# RF08nv.net
KiCad netlist of a schematic drawn in EAGLE
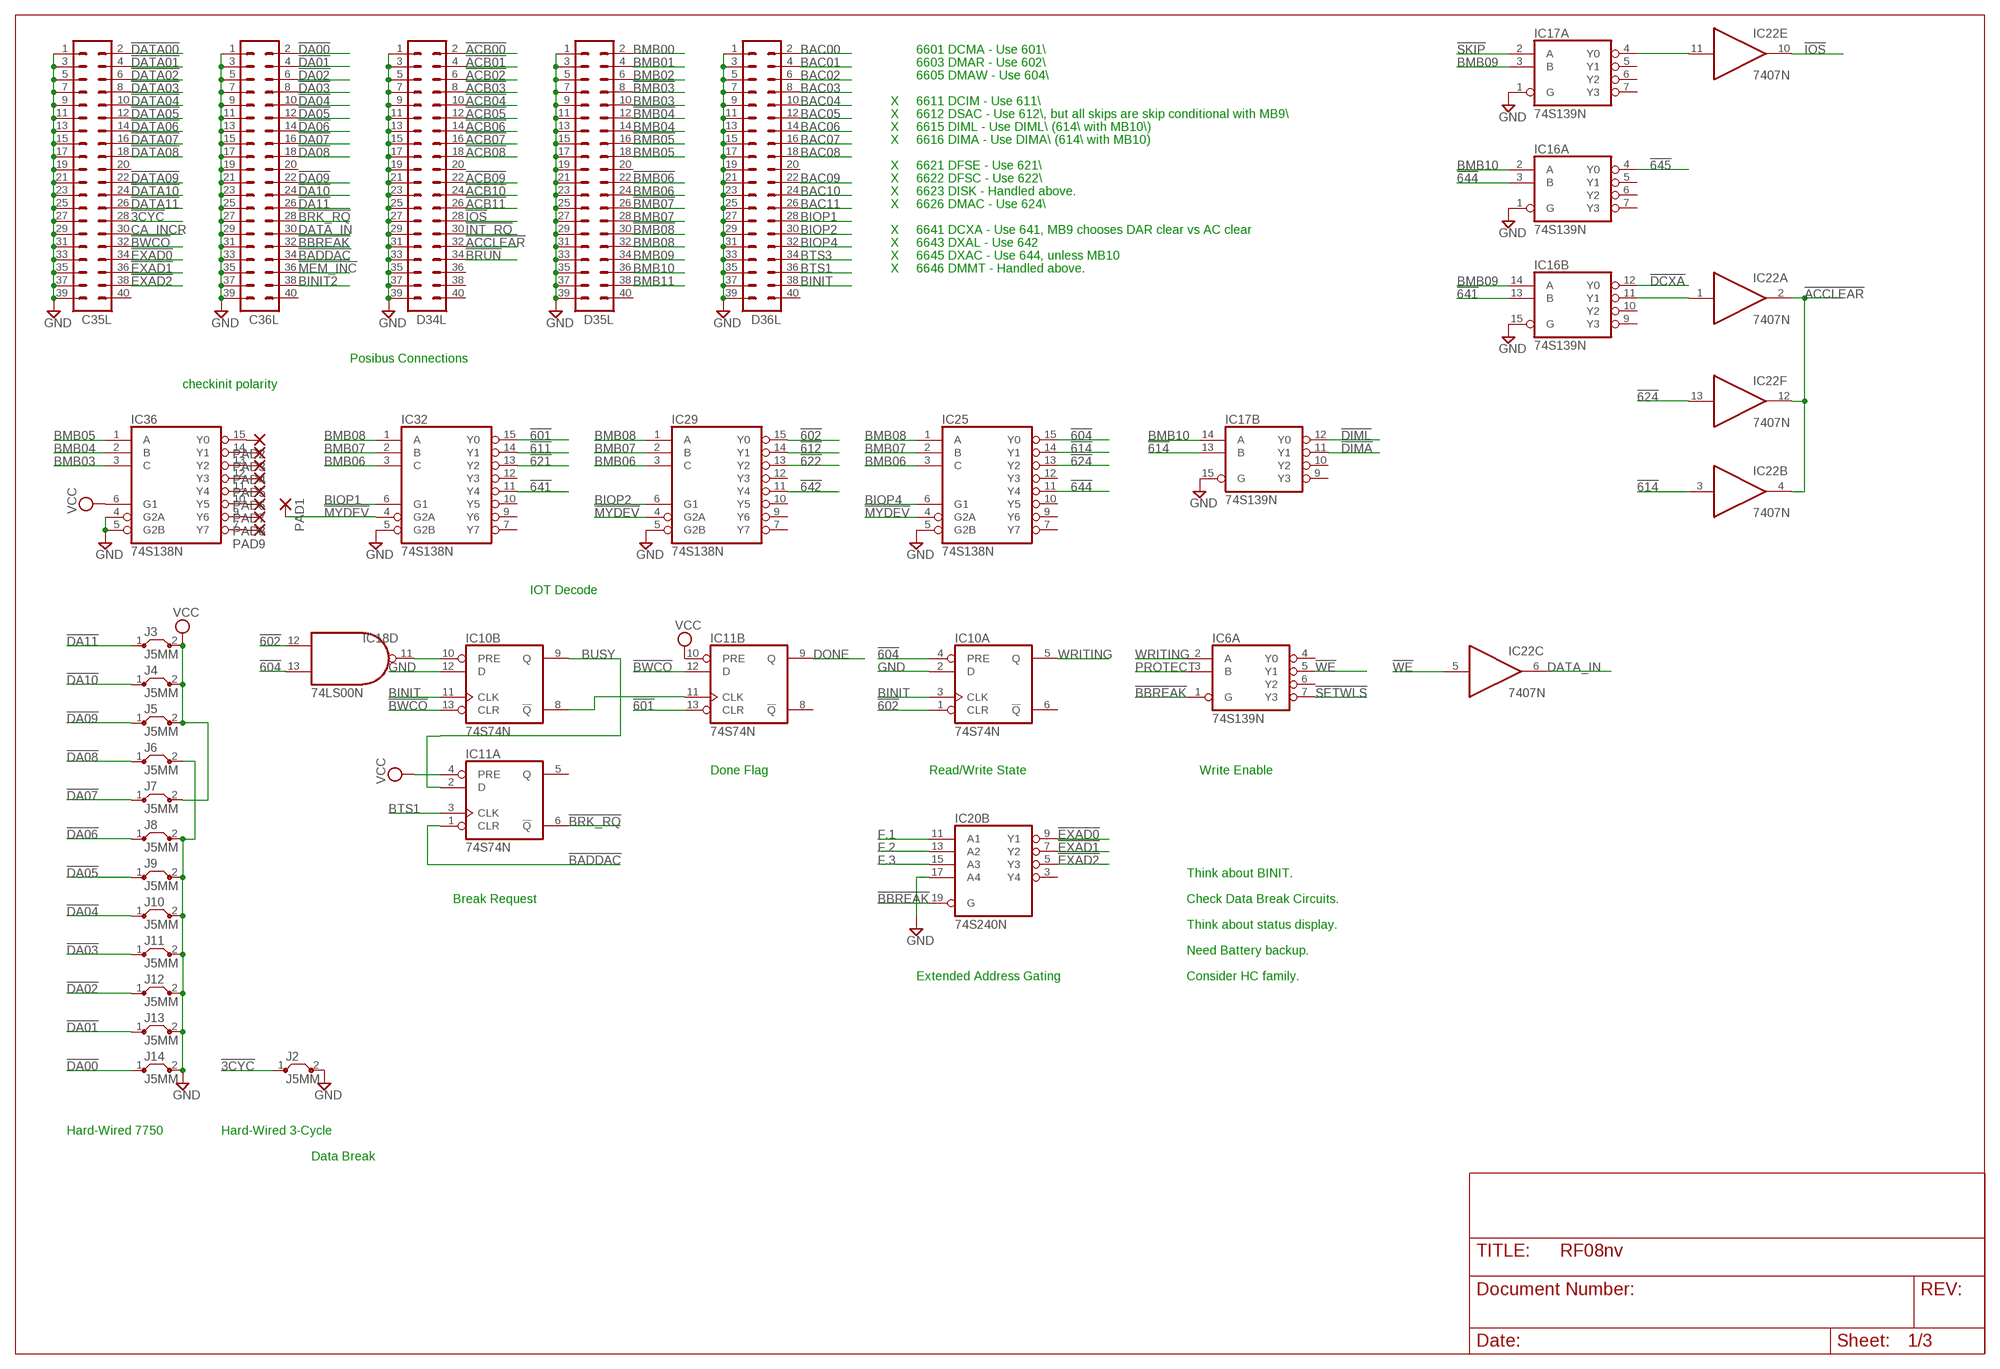
[diagram p0: schematic, sheet 1]
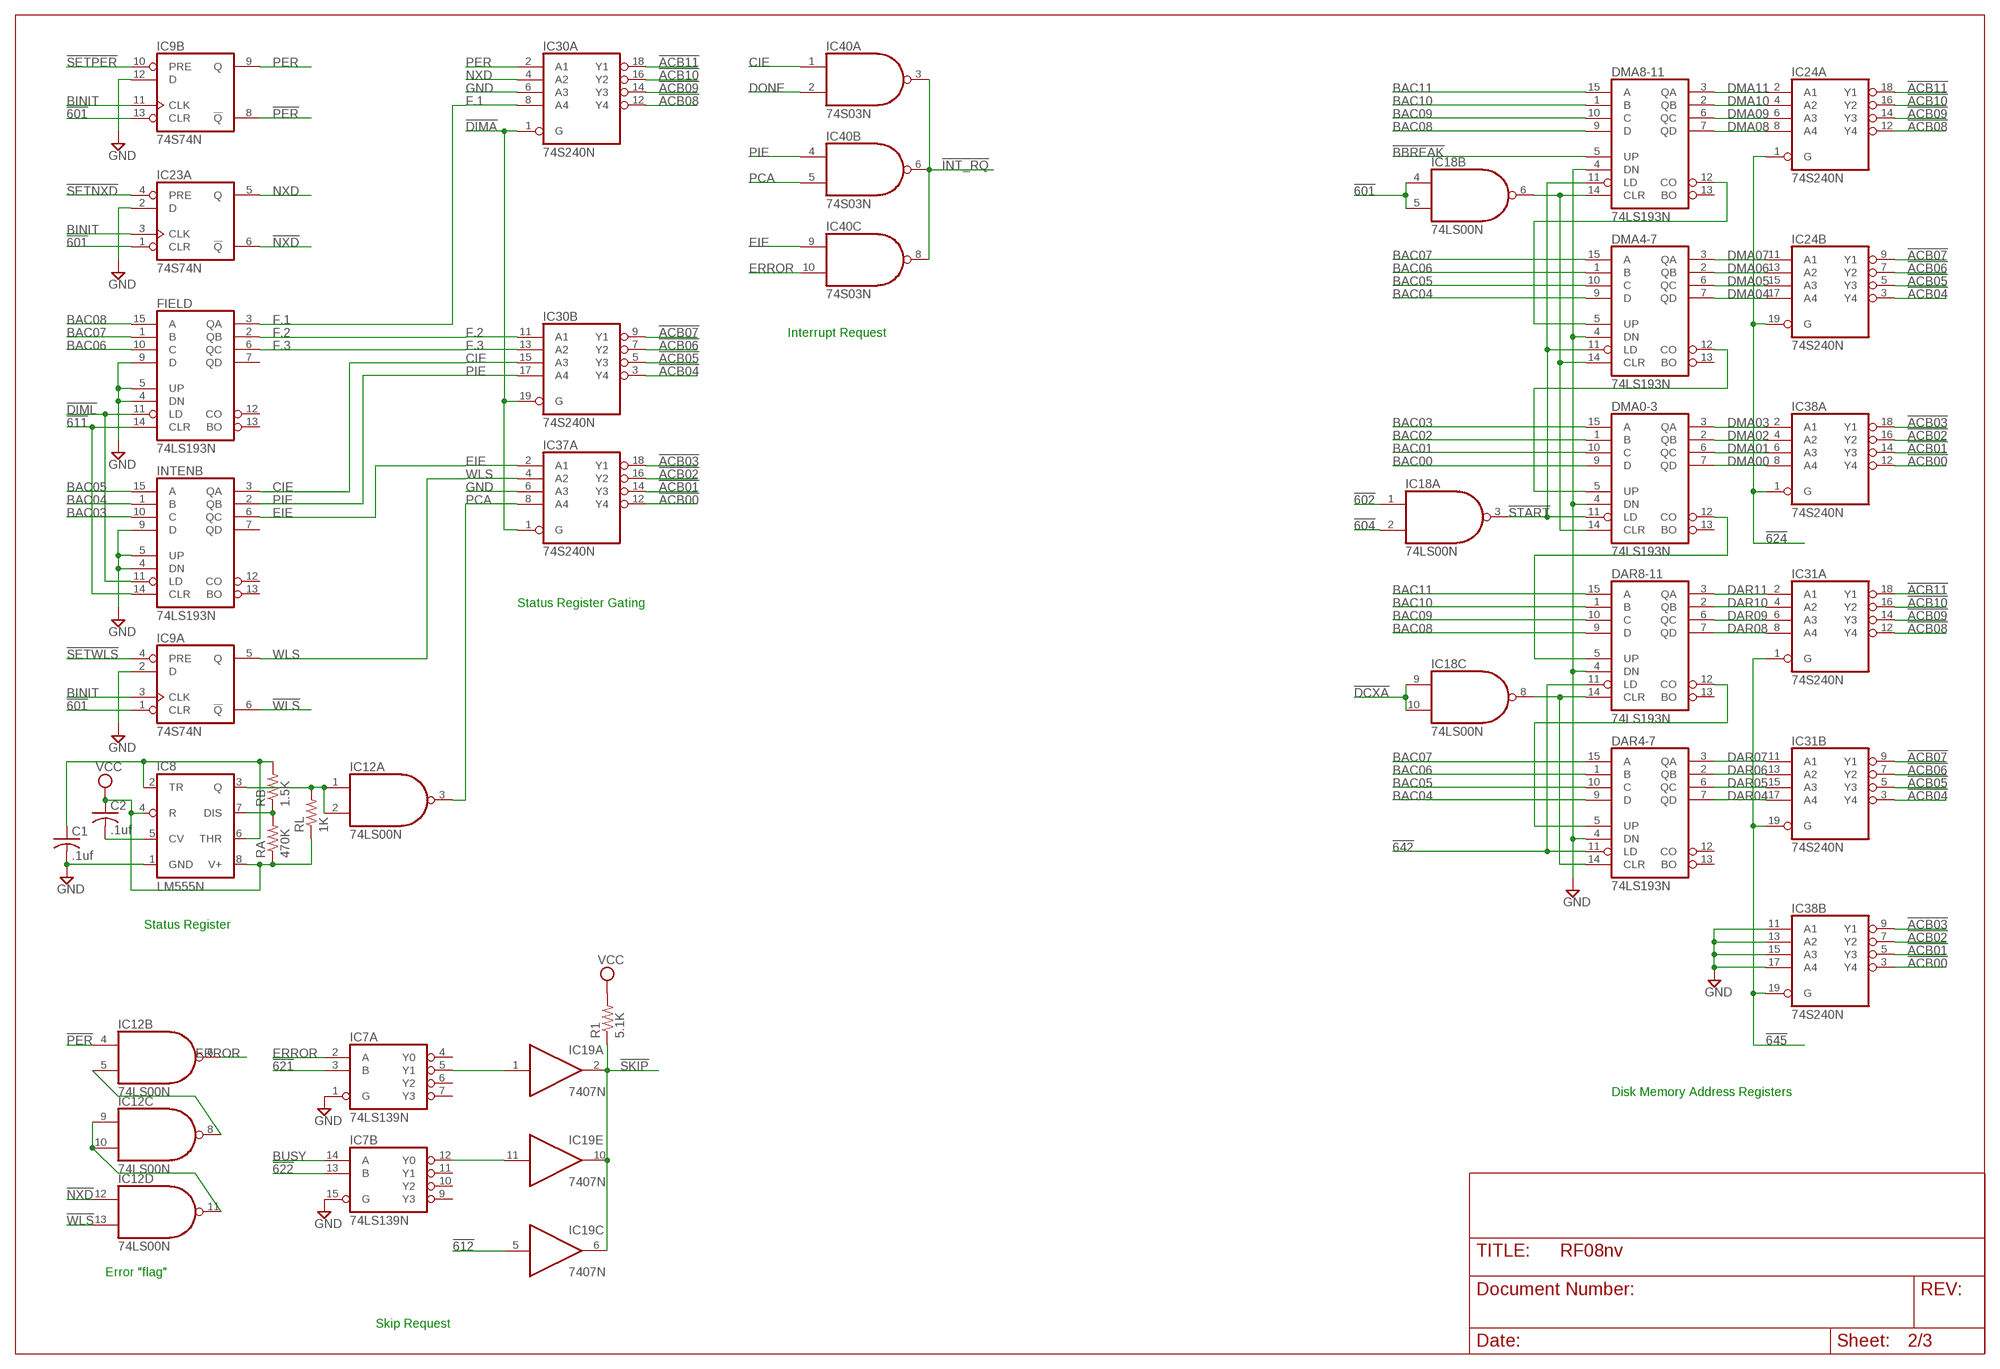
[diagram p1: schematic, sheet 2]
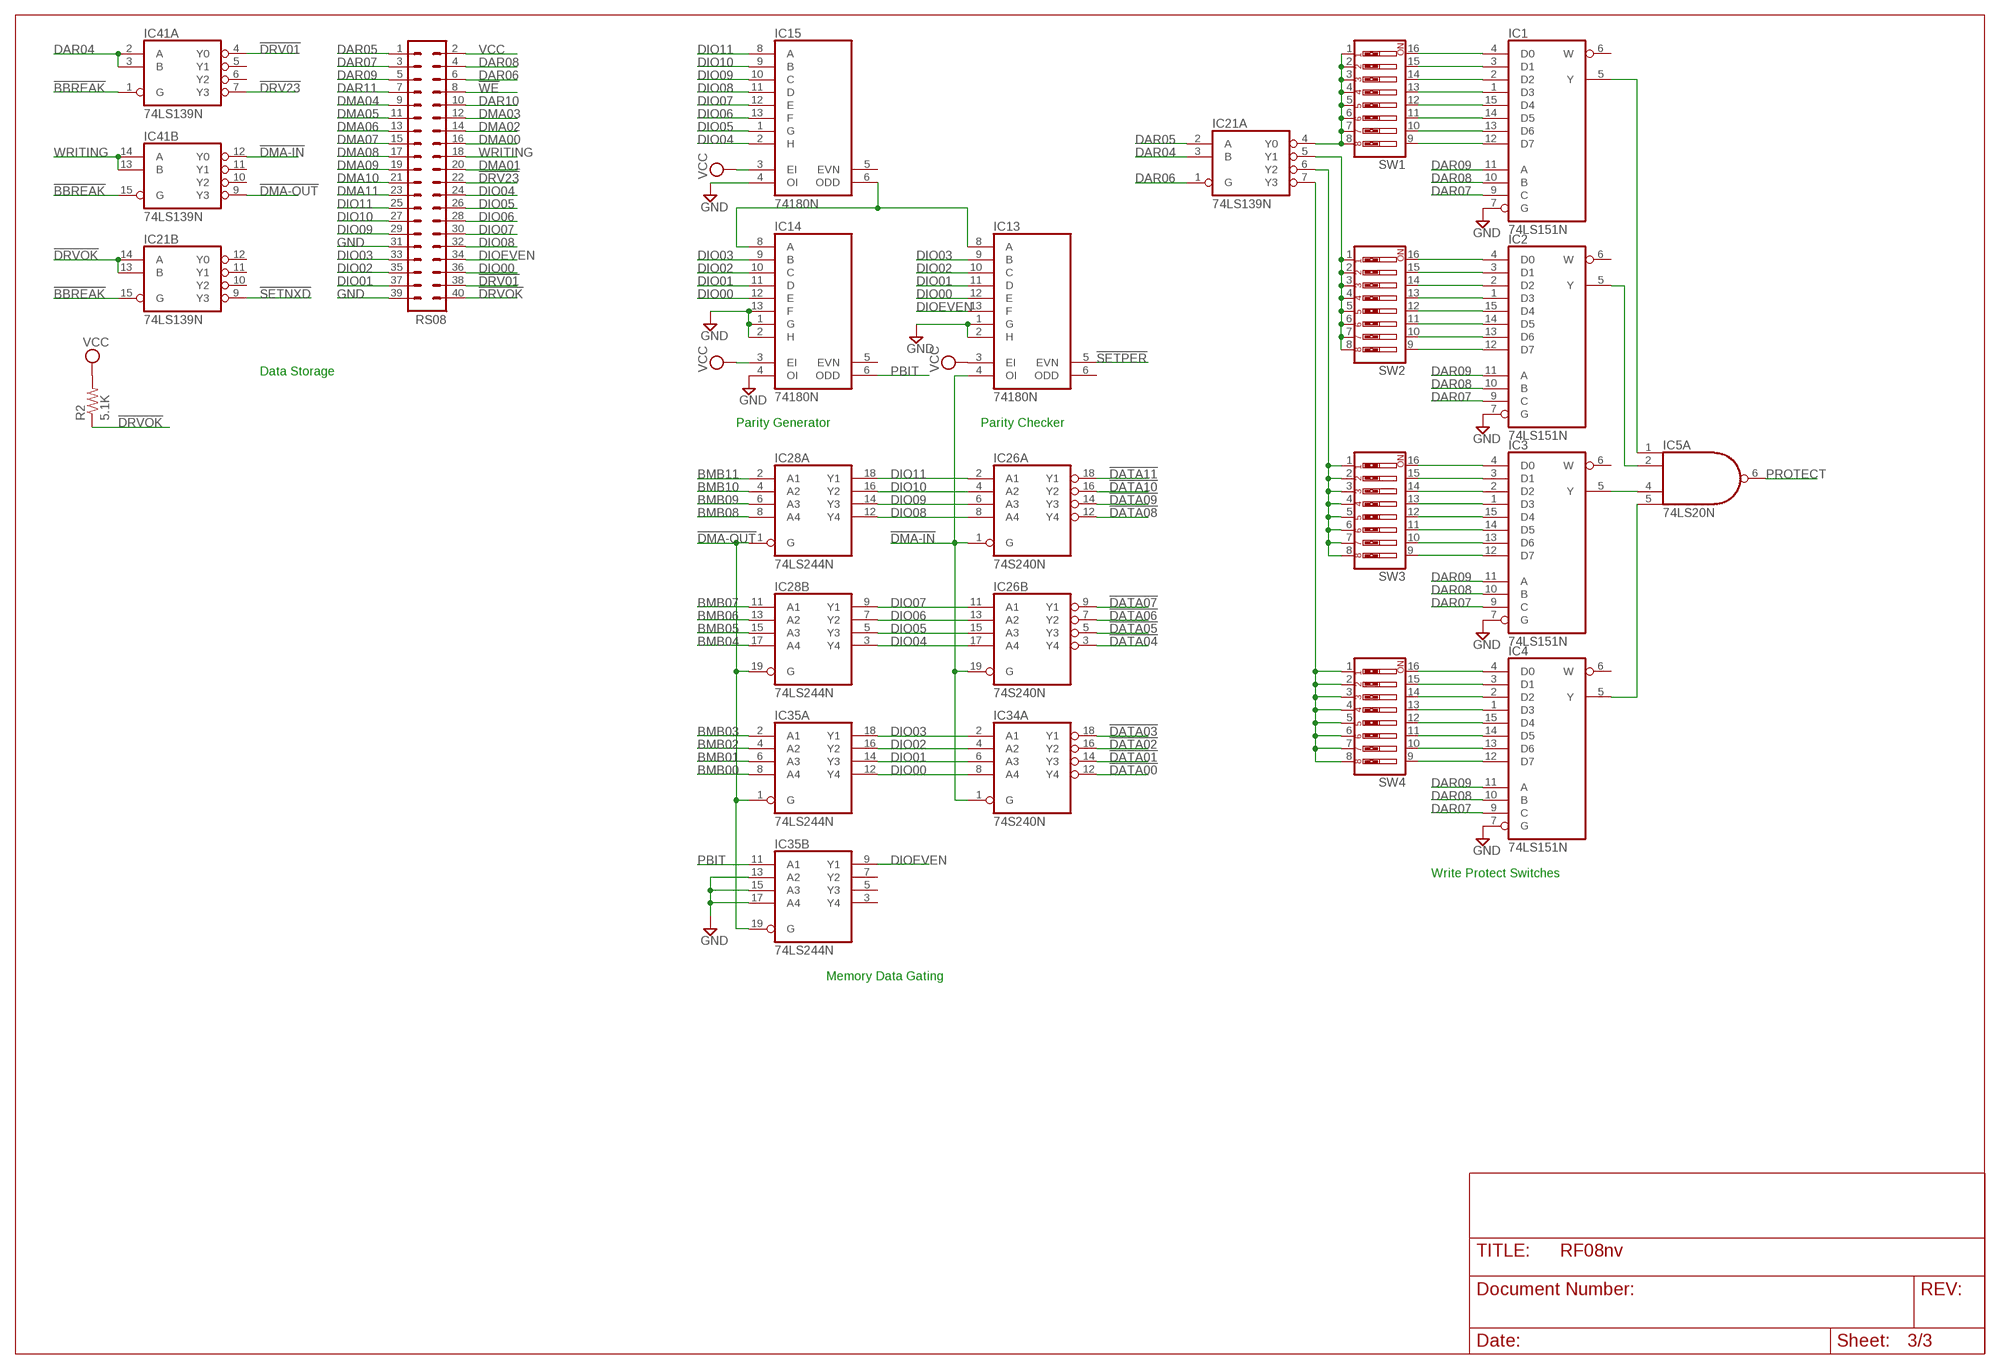
[diagram p2: schematic, sheet 3]

(export (version "E")
  (design (tool "Eeschema 10.0.6"))
  (components
    (comp (ref "IC1")
      (value "74LS151N")
      (footprint "eagle-import:DIL16")
      (libsource (lib "eagle-import") (part "74151NLS"))
    )
    (comp (ref "IC2")
      (value "74LS151N")
      (footprint "eagle-import:DIL16")
      (libsource (lib "eagle-import") (part "74151NLS"))
    )
    (comp (ref "IC3")
      (value "74LS151N")
      (footprint "eagle-import:DIL16")
      (libsource (lib "eagle-import") (part "74151NLS"))
    )
    (comp (ref "IC4")
      (value "74LS151N")
      (footprint "eagle-import:DIL16")
      (libsource (lib "eagle-import") (part "74151NLS"))
    )
    (comp (ref "IC5")
      (value "74LS20N")
      (footprint "eagle-import:DIL14")
      (libsource (lib "eagle-import") (part "7420NLS"))
    )
    (comp (ref "IC13")
      (value "74180N")
      (footprint "eagle-import:DIL14")
      (libsource (lib "eagle-import") (part "74180N"))
    )
    (comp (ref "IC14")
      (value "74180N")
      (footprint "eagle-import:DIL14")
      (libsource (lib "eagle-import") (part "74180N"))
    )
    (comp (ref "IC15")
      (value "74180N")
      (footprint "eagle-import:DIL14")
      (libsource (lib "eagle-import") (part "74180N"))
    )
    (comp (ref "IC21")
      (value "74LS139N")
      (footprint "eagle-import:DIL16")
      (libsource (lib "eagle-import") (part "74139NLS"))
    )
    (comp (ref "IC26")
      (value "74S240N")
      (footprint "eagle-import:DIL20")
      (libsource (lib "eagle-import") (part "74240NS"))
    )
    (comp (ref "IC28")
      (value "74LS244N")
      (footprint "eagle-import:DIL20")
      (libsource (lib "eagle-import") (part "74244NLS"))
    )
    (comp (ref "IC34")
      (value "74S240N")
      (footprint "eagle-import:DIL20")
      (libsource (lib "eagle-import") (part "74240NS"))
    )
    (comp (ref "IC35")
      (value "74LS244N")
      (footprint "eagle-import:DIL20")
      (libsource (lib "eagle-import") (part "74244NLS"))
    )
    (comp (ref "IC41")
      (value "74LS139N")
      (footprint "eagle-import:DIL16")
      (libsource (lib "eagle-import") (part "74139NLS"))
    )
    (comp (ref "R2")
      (value "5.1K")
      (footprint "eagle-import:0207_10")
      (libsource (lib "eagle-import") (part "R-US_0207/10"))
    )
    (comp (ref "RS08")
      (value "MA20-2")
      (footprint "eagle-import:MA20-2")
      (libsource (lib "eagle-import") (part "MA20-2"))
    )
    (comp (ref "SW1")
      (value "SW_DIP-8")
      (footprint "eagle-import:EDG-08")
      (libsource (lib "eagle-import") (part "SW_DIP-8"))
    )
    (comp (ref "SW2")
      (value "SW_DIP-8")
      (footprint "eagle-import:EDG-08")
      (libsource (lib "eagle-import") (part "SW_DIP-8"))
    )
    (comp (ref "SW3")
      (value "SW_DIP-8")
      (footprint "eagle-import:EDG-08")
      (libsource (lib "eagle-import") (part "SW_DIP-8"))
    )
    (comp (ref "SW4")
      (value "SW_DIP-8")
      (footprint "eagle-import:EDG-08")
      (libsource (lib "eagle-import") (part "SW_DIP-8"))
    )
    (comp (ref "C1")
      (value ".1uf")
      (footprint "eagle-import:C050-025X075")
      (libsource (lib "eagle-import") (part "C-US050-025X075"))
    )
    (comp (ref "C2")
      (value ".1uf")
      (footprint "eagle-import:C050-025X075")
      (libsource (lib "eagle-import") (part "C-US050-025X075"))
    )
    (comp (ref "DAR4-7")
      (value "74LS193N")
      (footprint "eagle-import:DIL16")
      (libsource (lib "eagle-import") (part "74192NLS"))
    )
    (comp (ref "DAR8-11")
      (value "74LS193N")
      (footprint "eagle-import:DIL16")
      (libsource (lib "eagle-import") (part "74192NLS"))
    )
    (comp (ref "DMA0-3")
      (value "74LS193N")
      (footprint "eagle-import:DIL16")
      (libsource (lib "eagle-import") (part "74192NLS"))
    )
    (comp (ref "DMA4-7")
      (value "74LS193N")
      (footprint "eagle-import:DIL16")
      (libsource (lib "eagle-import") (part "74192NLS"))
    )
    (comp (ref "DMA8-11")
      (value "74LS193N")
      (footprint "eagle-import:DIL16")
      (libsource (lib "eagle-import") (part "74192NLS"))
    )
    (comp (ref "FIELD")
      (value "74LS193N")
      (footprint "eagle-import:DIL16")
      (libsource (lib "eagle-import") (part "74192NLS"))
    )
    (comp (ref "IC7")
      (value "74LS139N")
      (footprint "eagle-import:DIL16")
      (libsource (lib "eagle-import") (part "74139NLS"))
    )
    (comp (ref "IC8")
      (value "LM555N")
      (footprint "eagle-import:DIL08")
      (libsource (lib "eagle-import") (part "555NLM"))
    )
    (comp (ref "IC9")
      (value "74S74N")
      (footprint "eagle-import:DIL14")
      (libsource (lib "eagle-import") (part "7474NS"))
    )
    (comp (ref "IC12")
      (value "74LS00N")
      (footprint "eagle-import:DIL14")
      (libsource (lib "eagle-import") (part "7400NLS"))
    )
    (comp (ref "IC18")
      (value "74LS00N")
      (footprint "eagle-import:DIL14")
      (libsource (lib "eagle-import") (part "7400NLS"))
    )
    (comp (ref "IC19")
      (value "7407N")
      (footprint "eagle-import:DIL14")
      (libsource (lib "eagle-import") (part "7407N"))
    )
    (comp (ref "IC23")
      (value "74S74N")
      (footprint "eagle-import:DIL14")
      (libsource (lib "eagle-import") (part "7474NS"))
    )
    (comp (ref "IC24")
      (value "74S240N")
      (footprint "eagle-import:DIL20")
      (libsource (lib "eagle-import") (part "74240NS"))
    )
    (comp (ref "IC30")
      (value "74S240N")
      (footprint "eagle-import:DIL20")
      (libsource (lib "eagle-import") (part "74240NS"))
    )
    (comp (ref "IC31")
      (value "74S240N")
      (footprint "eagle-import:DIL20")
      (libsource (lib "eagle-import") (part "74240NS"))
    )
    (comp (ref "IC37")
      (value "74S240N")
      (footprint "eagle-import:DIL20")
      (libsource (lib "eagle-import") (part "74240NS"))
    )
    (comp (ref "IC38")
      (value "74S240N")
      (footprint "eagle-import:DIL20")
      (libsource (lib "eagle-import") (part "74240NS"))
    )
    (comp (ref "IC40")
      (value "74S03N")
      (footprint "eagle-import:DIL14")
      (libsource (lib "eagle-import") (part "7403NS"))
    )
    (comp (ref "INTENB")
      (value "74LS193N")
      (footprint "eagle-import:DIL16")
      (libsource (lib "eagle-import") (part "74192NLS"))
    )
    (comp (ref "R1")
      (value "5.1K")
      (footprint "eagle-import:0207_10")
      (libsource (lib "eagle-import") (part "R-US_0207/10"))
    )
    (comp (ref "RA")
      (value "470K")
      (footprint "eagle-import:0207_10")
      (libsource (lib "eagle-import") (part "R-US_0207/10"))
    )
    (comp (ref "RB")
      (value "1.5K")
      (footprint "eagle-import:0207_10")
      (libsource (lib "eagle-import") (part "R-US_0207/10"))
    )
    (comp (ref "RL")
      (value "1K")
      (footprint "eagle-import:0207_10")
      (libsource (lib "eagle-import") (part "R-US_0207/10"))
    )
    (comp (ref "C35L")
      (value "MA20-2")
      (footprint "eagle-import:MA20-2")
      (libsource (lib "eagle-import") (part "MA20-2"))
    )
    (comp (ref "C36L")
      (value "MA20-2")
      (footprint "eagle-import:MA20-2")
      (libsource (lib "eagle-import") (part "MA20-2"))
    )
    (comp (ref "D34L")
      (value "MA20-2")
      (footprint "eagle-import:MA20-2")
      (libsource (lib "eagle-import") (part "MA20-2"))
    )
    (comp (ref "D35L")
      (value "MA20-2")
      (footprint "eagle-import:MA20-2")
      (libsource (lib "eagle-import") (part "MA20-2"))
    )
    (comp (ref "D36L")
      (value "MA20-2")
      (footprint "eagle-import:MA20-2")
      (libsource (lib "eagle-import") (part "MA20-2"))
    )
    (comp (ref "IC6")
      (value "74S139N")
      (footprint "eagle-import:DIL16")
      (libsource (lib "eagle-import") (part "74139NS"))
    )
    (comp (ref "IC10")
      (value "74S74N")
      (footprint "eagle-import:DIL14")
      (libsource (lib "eagle-import") (part "7474NS"))
    )
    (comp (ref "IC11")
      (value "74S74N")
      (footprint "eagle-import:DIL14")
      (libsource (lib "eagle-import") (part "7474NS"))
    )
    (comp (ref "IC16")
      (value "74S139N")
      (footprint "eagle-import:DIL16")
      (libsource (lib "eagle-import") (part "74139NS"))
    )
    (comp (ref "IC17")
      (value "74S139N")
      (footprint "eagle-import:DIL16")
      (libsource (lib "eagle-import") (part "74139NS"))
    )
    (comp (ref "IC20")
      (value "74S240N")
      (footprint "eagle-import:DIL20")
      (libsource (lib "eagle-import") (part "74240NS"))
    )
    (comp (ref "IC22")
      (value "7407N")
      (footprint "eagle-import:DIL14")
      (libsource (lib "eagle-import") (part "7407N"))
    )
    (comp (ref "IC25")
      (value "74S138N")
      (footprint "eagle-import:DIL16")
      (libsource (lib "eagle-import") (part "74138NS"))
    )
    (comp (ref "IC29")
      (value "74S138N")
      (footprint "eagle-import:DIL16")
      (libsource (lib "eagle-import") (part "74138NS"))
    )
    (comp (ref "IC32")
      (value "74S138N")
      (footprint "eagle-import:DIL16")
      (libsource (lib "eagle-import") (part "74138NS"))
    )
    (comp (ref "IC36")
      (value "74S138N")
      (footprint "eagle-import:DIL16")
      (libsource (lib "eagle-import") (part "74138NS"))
    )
    (comp (ref "J2")
      (value "J5MM")
      (footprint "eagle-import:05")
      (libsource (lib "eagle-import") (part "J5MM"))
    )
    (comp (ref "J3")
      (value "J5MM")
      (footprint "eagle-import:05")
      (libsource (lib "eagle-import") (part "J5MM"))
    )
    (comp (ref "J4")
      (value "J5MM")
      (footprint "eagle-import:05")
      (libsource (lib "eagle-import") (part "J5MM"))
    )
    (comp (ref "J5")
      (value "J5MM")
      (footprint "eagle-import:05")
      (libsource (lib "eagle-import") (part "J5MM"))
    )
    (comp (ref "J6")
      (value "J5MM")
      (footprint "eagle-import:05")
      (libsource (lib "eagle-import") (part "J5MM"))
    )
    (comp (ref "J7")
      (value "J5MM")
      (footprint "eagle-import:05")
      (libsource (lib "eagle-import") (part "J5MM"))
    )
    (comp (ref "J8")
      (value "J5MM")
      (footprint "eagle-import:05")
      (libsource (lib "eagle-import") (part "J5MM"))
    )
    (comp (ref "J9")
      (value "J5MM")
      (footprint "eagle-import:05")
      (libsource (lib "eagle-import") (part "J5MM"))
    )
    (comp (ref "J10")
      (value "J5MM")
      (footprint "eagle-import:05")
      (libsource (lib "eagle-import") (part "J5MM"))
    )
    (comp (ref "J11")
      (value "J5MM")
      (footprint "eagle-import:05")
      (libsource (lib "eagle-import") (part "J5MM"))
    )
    (comp (ref "J12")
      (value "J5MM")
      (footprint "eagle-import:05")
      (libsource (lib "eagle-import") (part "J5MM"))
    )
    (comp (ref "J13")
      (value "J5MM")
      (footprint "eagle-import:05")
      (libsource (lib "eagle-import") (part "J5MM"))
    )
    (comp (ref "J14")
      (value "J5MM")
      (footprint "eagle-import:05")
      (libsource (lib "eagle-import") (part "J5MM"))
    )
    (comp (ref "PAD1")
      (value "1,6/0,8")
      (footprint "eagle-import:1,6_0,8")
      (libsource (lib "eagle-import") (part "1,6/0,8"))
    )
    (comp (ref "PAD2")
      (value "1,6/0,8")
      (footprint "eagle-import:1,6_0,8")
      (libsource (lib "eagle-import") (part "1,6/0,8"))
    )
    (comp (ref "PAD3")
      (value "1,6/0,8")
      (footprint "eagle-import:1,6_0,8")
      (libsource (lib "eagle-import") (part "1,6/0,8"))
    )
    (comp (ref "PAD4")
      (value "1,6/0,8")
      (footprint "eagle-import:1,6_0,8")
      (libsource (lib "eagle-import") (part "1,6/0,8"))
    )
    (comp (ref "PAD5")
      (value "1,6/0,8")
      (footprint "eagle-import:1,6_0,8")
      (libsource (lib "eagle-import") (part "1,6/0,8"))
    )
    (comp (ref "PAD6")
      (value "1,6/0,8")
      (footprint "eagle-import:1,6_0,8")
      (libsource (lib "eagle-import") (part "1,6/0,8"))
    )
    (comp (ref "PAD7")
      (value "1,6/0,8")
      (footprint "eagle-import:1,6_0,8")
      (libsource (lib "eagle-import") (part "1,6/0,8"))
    )
    (comp (ref "PAD8")
      (value "1,6/0,8")
      (footprint "eagle-import:1,6_0,8")
      (libsource (lib "eagle-import") (part "1,6/0,8"))
    )
    (comp (ref "PAD9")
      (value "1,6/0,8")
      (footprint "eagle-import:1,6_0,8")
      (libsource (lib "eagle-import") (part "1,6/0,8"))
    )
  )
  (nets
    (net (code "1") (name "BAC00") (class "Default")
      (node (ref "D36L") (pin "2") (pinfunction "2_2") (pintype "passive"))
      (node (ref "DMA0-3") (pin "9") (pinfunction "D_9") (pintype "input"))
    )
    (net (code "2") (name "BAC01") (class "Default")
      (node (ref "D36L") (pin "4") (pinfunction "4_4") (pintype "passive"))
      (node (ref "DMA0-3") (pin "10") (pinfunction "C_10") (pintype "input"))
    )
    (net (code "3") (name "BAC02") (class "Default")
      (node (ref "D36L") (pin "6") (pinfunction "6_6") (pintype "passive"))
      (node (ref "DMA0-3") (pin "1") (pinfunction "B_1") (pintype "input"))
    )
    (net (code "4") (name "BAC03") (class "Default")
      (node (ref "D36L") (pin "8") (pinfunction "8_8") (pintype "passive"))
      (node (ref "DMA0-3") (pin "15") (pinfunction "A_15") (pintype "input"))
      (node (ref "INTENB") (pin "10") (pinfunction "C_10") (pintype "input"))
    )
    (net (code "5") (name "BAC04") (class "Default")
      (node (ref "D36L") (pin "10") (pinfunction "10_10") (pintype "passive"))
      (node (ref "DAR4-7") (pin "9") (pinfunction "D_9") (pintype "input"))
      (node (ref "DMA4-7") (pin "9") (pinfunction "D_9") (pintype "input"))
      (node (ref "INTENB") (pin "1") (pinfunction "B_1") (pintype "input"))
    )
    (net (code "6") (name "BAC05") (class "Default")
      (node (ref "D36L") (pin "12") (pinfunction "12_12") (pintype "passive"))
      (node (ref "DAR4-7") (pin "10") (pinfunction "C_10") (pintype "input"))
      (node (ref "DMA4-7") (pin "10") (pinfunction "C_10") (pintype "input"))
      (node (ref "INTENB") (pin "15") (pinfunction "A_15") (pintype "input"))
    )
    (net (code "7") (name "BAC06") (class "Default")
      (node (ref "D36L") (pin "14") (pinfunction "14_14") (pintype "passive"))
      (node (ref "DAR4-7") (pin "1") (pinfunction "B_1") (pintype "input"))
      (node (ref "DMA4-7") (pin "1") (pinfunction "B_1") (pintype "input"))
      (node (ref "FIELD") (pin "10") (pinfunction "C_10") (pintype "input"))
    )
    (net (code "8") (name "BAC07") (class "Default")
      (node (ref "D36L") (pin "16") (pinfunction "16_16") (pintype "passive"))
      (node (ref "DAR4-7") (pin "15") (pinfunction "A_15") (pintype "input"))
      (node (ref "DMA4-7") (pin "15") (pinfunction "A_15") (pintype "input"))
      (node (ref "FIELD") (pin "1") (pinfunction "B_1") (pintype "input"))
    )
    (net (code "9") (name "BAC08") (class "Default")
      (node (ref "D36L") (pin "18") (pinfunction "18_18") (pintype "passive"))
      (node (ref "DAR8-11") (pin "9") (pinfunction "D_9") (pintype "input"))
      (node (ref "DMA8-11") (pin "9") (pinfunction "D_9") (pintype "input"))
      (node (ref "FIELD") (pin "15") (pinfunction "A_15") (pintype "input"))
    )
    (net (code "10") (name "BAC09") (class "Default")
      (node (ref "D36L") (pin "22") (pinfunction "22_22") (pintype "passive"))
      (node (ref "DAR8-11") (pin "10") (pinfunction "C_10") (pintype "input"))
      (node (ref "DMA8-11") (pin "10") (pinfunction "C_10") (pintype "input"))
    )
    (net (code "11") (name "BAC10") (class "Default")
      (node (ref "D36L") (pin "24") (pinfunction "24_24") (pintype "passive"))
      (node (ref "DAR8-11") (pin "1") (pinfunction "B_1") (pintype "input"))
      (node (ref "DMA8-11") (pin "1") (pinfunction "B_1") (pintype "input"))
    )
    (net (code "12") (name "BAC11") (class "Default")
      (node (ref "D36L") (pin "26") (pinfunction "26_26") (pintype "passive"))
      (node (ref "DAR8-11") (pin "15") (pinfunction "A_15") (pintype "input"))
      (node (ref "DMA8-11") (pin "15") (pinfunction "A_15") (pintype "input"))
    )
    (net (code "13") (name "BINIT") (class "Default")
      (node (ref "D36L") (pin "38") (pinfunction "38_38") (pintype "passive"))
      (node (ref "IC10") (pin "11") (pinfunction "CLK_11") (pintype "input"))
      (node (ref "IC10") (pin "3") (pinfunction "CLK_3") (pintype "input"))
      (node (ref "IC23") (pin "3") (pinfunction "CLK_3") (pintype "input"))
      (node (ref "IC9") (pin "11") (pinfunction "CLK_11") (pintype "input"))
      (node (ref "IC9") (pin "3") (pinfunction "CLK_3") (pintype "input"))
    )
    (net (code "14") (name "BINIT2") (class "Default")
      (node (ref "C36L") (pin "38") (pinfunction "38_38") (pintype "passive"))
    )
    (net (code "15") (name "BIOP1") (class "Default")
      (node (ref "D36L") (pin "28") (pinfunction "28_28") (pintype "passive"))
      (node (ref "IC32") (pin "6") (pinfunction "G1_6") (pintype "input"))
    )
    (net (code "16") (name "BIOP2") (class "Default")
      (node (ref "D36L") (pin "30") (pinfunction "30_30") (pintype "passive"))
      (node (ref "IC29") (pin "6") (pinfunction "G1_6") (pintype "input"))
    )
    (net (code "17") (name "BIOP4") (class "Default")
      (node (ref "D36L") (pin "32") (pinfunction "32_32") (pintype "passive"))
      (node (ref "IC25") (pin "6") (pinfunction "G1_6") (pintype "input"))
    )
    (net (code "18") (name "BMB00") (class "Default")
      (node (ref "D35L") (pin "2") (pinfunction "2_2") (pintype "passive"))
      (node (ref "IC35") (pin "8") (pinfunction "A4_8") (pintype "input"))
    )
    (net (code "19") (name "BMB01") (class "Default")
      (node (ref "D35L") (pin "4") (pinfunction "4_4") (pintype "passive"))
      (node (ref "IC35") (pin "6") (pinfunction "A3_6") (pintype "input"))
    )
    (net (code "20") (name "BMB02") (class "Default")
      (node (ref "D35L") (pin "6") (pinfunction "6_6") (pintype "passive"))
      (node (ref "IC35") (pin "4") (pinfunction "A2_4") (pintype "input"))
    )
    (net (code "21") (name "BMB03") (class "Default")
      (node (ref "D35L") (pin "10") (pinfunction "10_10") (pintype "passive"))
      (node (ref "IC35") (pin "2") (pinfunction "A1_2") (pintype "input"))
      (node (ref "IC36") (pin "3") (pinfunction "C_3") (pintype "input"))
    )
    (net (code "22") (name "BMB04") (class "Default")
      (node (ref "D35L") (pin "14") (pinfunction "14_14") (pintype "passive"))
      (node (ref "IC28") (pin "17") (pinfunction "A4_17") (pintype "input"))
      (node (ref "IC36") (pin "2") (pinfunction "B_2") (pintype "input"))
    )
    (net (code "23") (name "BMB05") (class "Default")
      (node (ref "D35L") (pin "18") (pinfunction "18_18") (pintype "passive"))
      (node (ref "IC28") (pin "15") (pinfunction "A3_15") (pintype "input"))
      (node (ref "IC36") (pin "1") (pinfunction "A_1") (pintype "input"))
    )
    (net (code "24") (name "BMB06") (class "Default")
      (node (ref "D35L") (pin "24") (pinfunction "24_24") (pintype "passive"))
      (node (ref "IC25") (pin "3") (pinfunction "C_3") (pintype "input"))
      (node (ref "IC28") (pin "13") (pinfunction "A2_13") (pintype "input"))
      (node (ref "IC29") (pin "3") (pinfunction "C_3") (pintype "input"))
      (node (ref "IC32") (pin "3") (pinfunction "C_3") (pintype "input"))
    )
    (net (code "25") (name "BMB07") (class "Default")
      (node (ref "D35L") (pin "28") (pinfunction "28_28") (pintype "passive"))
      (node (ref "IC25") (pin "2") (pinfunction "B_2") (pintype "input"))
      (node (ref "IC28") (pin "11") (pinfunction "A1_11") (pintype "input"))
      (node (ref "IC29") (pin "2") (pinfunction "B_2") (pintype "input"))
      (node (ref "IC32") (pin "2") (pinfunction "B_2") (pintype "input"))
    )
    (net (code "26") (name "BMB08") (class "Default")
      (node (ref "D35L") (pin "32") (pinfunction "32_32") (pintype "passive"))
      (node (ref "IC25") (pin "1") (pinfunction "A_1") (pintype "input"))
      (node (ref "IC28") (pin "8") (pinfunction "A4_8") (pintype "input"))
      (node (ref "IC29") (pin "1") (pinfunction "A_1") (pintype "input"))
      (node (ref "IC32") (pin "1") (pinfunction "A_1") (pintype "input"))
    )
    (net (code "27") (name "BMB09") (class "Default")
      (node (ref "D35L") (pin "34") (pinfunction "34_34") (pintype "passive"))
      (node (ref "IC16") (pin "14") (pinfunction "A_14") (pintype "input"))
      (node (ref "IC17") (pin "3") (pinfunction "B_3") (pintype "input"))
      (node (ref "IC28") (pin "6") (pinfunction "A3_6") (pintype "input"))
    )
    (net (code "28") (name "BMB10") (class "Default")
      (node (ref "D35L") (pin "36") (pinfunction "36_36") (pintype "passive"))
      (node (ref "IC16") (pin "2") (pinfunction "A_2") (pintype "input"))
      (node (ref "IC17") (pin "14") (pinfunction "A_14") (pintype "input"))
      (node (ref "IC28") (pin "4") (pinfunction "A2_4") (pintype "input"))
    )
    (net (code "29") (name "BMB11") (class "Default")
      (node (ref "D35L") (pin "38") (pinfunction "38_38") (pintype "passive"))
      (node (ref "IC28") (pin "2") (pinfunction "A1_2") (pintype "input"))
    )
    (net (code "30") (name "BTS1") (class "Default")
      (node (ref "D36L") (pin "36") (pinfunction "36_36") (pintype "passive"))
      (node (ref "IC11") (pin "3") (pinfunction "CLK_3") (pintype "input"))
    )
    (net (code "31") (name "BTS3") (class "Default")
      (node (ref "D36L") (pin "34") (pinfunction "34_34") (pintype "passive"))
    )
    (net (code "32") (name "BUSY") (class "Default")
      (node (ref "IC10") (pin "9") (pinfunction "Q_9") (pintype "output"))
      (node (ref "IC11") (pin "2") (pinfunction "D_2") (pintype "input"))
      (node (ref "IC7") (pin "14") (pinfunction "A_14") (pintype "input"))
    )
    (net (code "33") (name "CA_INCR") (class "Default")
      (node (ref "C35L") (pin "30") (pinfunction "30_30") (pintype "passive"))
    )
    (net (code "34") (name "CIE") (class "Default")
      (node (ref "IC30") (pin "15") (pinfunction "A3_15") (pintype "input"))
      (node (ref "IC40") (pin "1") (pinfunction "I0_1") (pintype "input"))
      (node (ref "INTENB") (pin "3") (pinfunction "QA_3") (pintype "output"))
    )
    (net (code "35") (name "DAR04") (class "Default")
      (node (ref "DAR4-7") (pin "7") (pinfunction "QD_7") (pintype "output"))
      (node (ref "IC21") (pin "3") (pinfunction "B_3") (pintype "input"))
      (node (ref "IC31") (pin "17") (pinfunction "A4_17") (pintype "input"))
      (node (ref "IC41") (pin "2") (pinfunction "A_2") (pintype "input"))
      (node (ref "IC41") (pin "3") (pinfunction "B_3") (pintype "input"))
    )
    (net (code "36") (name "DAR05") (class "Default")
      (node (ref "DAR4-7") (pin "6") (pinfunction "QC_6") (pintype "output"))
      (node (ref "IC21") (pin "2") (pinfunction "A_2") (pintype "input"))
      (node (ref "IC31") (pin "15") (pinfunction "A3_15") (pintype "input"))
      (node (ref "RS08") (pin "1") (pinfunction "1_1") (pintype "passive"))
    )
    (net (code "37") (name "DAR06") (class "Default")
      (node (ref "DAR4-7") (pin "2") (pinfunction "QB_2") (pintype "output"))
      (node (ref "IC21") (pin "1") (pinfunction "G_1") (pintype "input"))
      (node (ref "IC31") (pin "13") (pinfunction "A2_13") (pintype "input"))
      (node (ref "RS08") (pin "6") (pinfunction "6_6") (pintype "passive"))
    )
    (net (code "38") (name "DAR07") (class "Default")
      (node (ref "DAR4-7") (pin "3") (pinfunction "QA_3") (pintype "output"))
      (node (ref "IC1") (pin "9") (pinfunction "C_9") (pintype "input"))
      (node (ref "IC2") (pin "9") (pinfunction "C_9") (pintype "input"))
      (node (ref "IC3") (pin "9") (pinfunction "C_9") (pintype "input"))
      (node (ref "IC31") (pin "11") (pinfunction "A1_11") (pintype "input"))
      (node (ref "IC4") (pin "9") (pinfunction "C_9") (pintype "input"))
      (node (ref "RS08") (pin "3") (pinfunction "3_3") (pintype "passive"))
    )
    (net (code "39") (name "DAR08") (class "Default")
      (node (ref "DAR8-11") (pin "7") (pinfunction "QD_7") (pintype "output"))
      (node (ref "IC1") (pin "10") (pinfunction "B_10") (pintype "input"))
      (node (ref "IC2") (pin "10") (pinfunction "B_10") (pintype "input"))
      (node (ref "IC3") (pin "10") (pinfunction "B_10") (pintype "input"))
      (node (ref "IC31") (pin "8") (pinfunction "A4_8") (pintype "input"))
      (node (ref "IC4") (pin "10") (pinfunction "B_10") (pintype "input"))
      (node (ref "RS08") (pin "4") (pinfunction "4_4") (pintype "passive"))
    )
    (net (code "40") (name "DAR09") (class "Default")
      (node (ref "DAR8-11") (pin "6") (pinfunction "QC_6") (pintype "output"))
      (node (ref "IC1") (pin "11") (pinfunction "A_11") (pintype "input"))
      (node (ref "IC2") (pin "11") (pinfunction "A_11") (pintype "input"))
      (node (ref "IC3") (pin "11") (pinfunction "A_11") (pintype "input"))
      (node (ref "IC31") (pin "6") (pinfunction "A3_6") (pintype "input"))
      (node (ref "IC4") (pin "11") (pinfunction "A_11") (pintype "input"))
      (node (ref "RS08") (pin "5") (pinfunction "5_5") (pintype "passive"))
    )
    (net (code "41") (name "DAR10") (class "Default")
      (node (ref "DAR8-11") (pin "2") (pinfunction "QB_2") (pintype "output"))
      (node (ref "IC31") (pin "4") (pinfunction "A2_4") (pintype "input"))
      (node (ref "RS08") (pin "10") (pinfunction "10_10") (pintype "passive"))
    )
    (net (code "42") (name "DAR11") (class "Default")
      (node (ref "DAR8-11") (pin "3") (pinfunction "QA_3") (pintype "output"))
      (node (ref "IC31") (pin "2") (pinfunction "A1_2") (pintype "input"))
      (node (ref "RS08") (pin "7") (pinfunction "7_7") (pintype "passive"))
    )
    (net (code "43") (name "DATA_IN") (class "Default")
      (node (ref "C36L") (pin "30") (pinfunction "30_30") (pintype "passive"))
      (node (ref "IC22") (pin "6") (pinfunction "O_6") (pintype "open_collector"))
    )
    (net (code "44") (name "DIO00") (class "Default")
      (node (ref "IC13") (pin "12") (pinfunction "E_12") (pintype "input"))
      (node (ref "IC14") (pin "12") (pinfunction "E_12") (pintype "input"))
      (node (ref "IC34") (pin "8") (pinfunction "A4_8") (pintype "input"))
      (node (ref "IC35") (pin "12") (pinfunction "Y4_12") (pintype "tri_state"))
      (node (ref "RS08") (pin "36") (pinfunction "36_36") (pintype "passive"))
    )
    (net (code "45") (name "DIO01") (class "Default")
      (node (ref "IC13") (pin "11") (pinfunction "D_11") (pintype "input"))
      (node (ref "IC14") (pin "11") (pinfunction "D_11") (pintype "input"))
      (node (ref "IC34") (pin "6") (pinfunction "A3_6") (pintype "input"))
      (node (ref "IC35") (pin "14") (pinfunction "Y3_14") (pintype "tri_state"))
      (node (ref "RS08") (pin "37") (pinfunction "37_37") (pintype "passive"))
    )
    (net (code "46") (name "DIO02") (class "Default")
      (node (ref "IC13") (pin "10") (pinfunction "C_10") (pintype "input"))
      (node (ref "IC14") (pin "10") (pinfunction "C_10") (pintype "input"))
      (node (ref "IC34") (pin "4") (pinfunction "A2_4") (pintype "input"))
      (node (ref "IC35") (pin "16") (pinfunction "Y2_16") (pintype "tri_state"))
      (node (ref "RS08") (pin "35") (pinfunction "35_35") (pintype "passive"))
    )
    (net (code "47") (name "DIO03") (class "Default")
      (node (ref "IC13") (pin "9") (pinfunction "B_9") (pintype "input"))
      (node (ref "IC14") (pin "9") (pinfunction "B_9") (pintype "input"))
      (node (ref "IC34") (pin "2") (pinfunction "A1_2") (pintype "input"))
      (node (ref "IC35") (pin "18") (pinfunction "Y1_18") (pintype "tri_state"))
      (node (ref "RS08") (pin "33") (pinfunction "33_33") (pintype "passive"))
    )
    (net (code "48") (name "DIO04") (class "Default")
      (node (ref "IC15") (pin "2") (pinfunction "H_2") (pintype "input"))
      (node (ref "IC26") (pin "17") (pinfunction "A4_17") (pintype "input"))
      (node (ref "IC28") (pin "3") (pinfunction "Y4_3") (pintype "tri_state"))
      (node (ref "RS08") (pin "24") (pinfunction "24_24") (pintype "passive"))
    )
    (net (code "49") (name "DIO05") (class "Default")
      (node (ref "IC15") (pin "1") (pinfunction "G_1") (pintype "input"))
      (node (ref "IC26") (pin "15") (pinfunction "A3_15") (pintype "input"))
      (node (ref "IC28") (pin "5") (pinfunction "Y3_5") (pintype "tri_state"))
      (node (ref "RS08") (pin "26") (pinfunction "26_26") (pintype "passive"))
    )
    (net (code "50") (name "DIO06") (class "Default")
      (node (ref "IC15") (pin "13") (pinfunction "F_13") (pintype "input"))
      (node (ref "IC26") (pin "13") (pinfunction "A2_13") (pintype "input"))
      (node (ref "IC28") (pin "7") (pinfunction "Y2_7") (pintype "tri_state"))
      (node (ref "RS08") (pin "28") (pinfunction "28_28") (pintype "passive"))
    )
    (net (code "51") (name "DIO07") (class "Default")
      (node (ref "IC15") (pin "12") (pinfunction "E_12") (pintype "input"))
      (node (ref "IC26") (pin "11") (pinfunction "A1_11") (pintype "input"))
      (node (ref "IC28") (pin "9") (pinfunction "Y1_9") (pintype "tri_state"))
      (node (ref "RS08") (pin "30") (pinfunction "30_30") (pintype "passive"))
    )
    (net (code "52") (name "DIO08") (class "Default")
      (node (ref "IC15") (pin "11") (pinfunction "D_11") (pintype "input"))
      (node (ref "IC26") (pin "8") (pinfunction "A4_8") (pintype "input"))
      (node (ref "IC28") (pin "12") (pinfunction "Y4_12") (pintype "tri_state"))
      (node (ref "RS08") (pin "32") (pinfunction "32_32") (pintype "passive"))
    )
    (net (code "53") (name "DIO09") (class "Default")
      (node (ref "IC15") (pin "10") (pinfunction "C_10") (pintype "input"))
      (node (ref "IC26") (pin "6") (pinfunction "A3_6") (pintype "input"))
      (node (ref "IC28") (pin "14") (pinfunction "Y3_14") (pintype "tri_state"))
      (node (ref "RS08") (pin "29") (pinfunction "29_29") (pintype "passive"))
    )
    (net (code "54") (name "DIO10") (class "Default")
      (node (ref "IC15") (pin "9") (pinfunction "B_9") (pintype "input"))
      (node (ref "IC26") (pin "4") (pinfunction "A2_4") (pintype "input"))
      (node (ref "IC28") (pin "16") (pinfunction "Y2_16") (pintype "tri_state"))
      (node (ref "RS08") (pin "27") (pinfunction "27_27") (pintype "passive"))
    )
    (net (code "55") (name "DIO11") (class "Default")
      (node (ref "IC15") (pin "8") (pinfunction "A_8") (pintype "input"))
      (node (ref "IC26") (pin "2") (pinfunction "A1_2") (pintype "input"))
      (node (ref "IC28") (pin "18") (pinfunction "Y1_18") (pintype "tri_state"))
      (node (ref "RS08") (pin "25") (pinfunction "25_25") (pintype "passive"))
    )
    (net (code "56") (name "DIOEVEN") (class "Default")
      (node (ref "IC13") (pin "13") (pinfunction "F_13") (pintype "input"))
      (node (ref "IC35") (pin "9") (pinfunction "Y1_9") (pintype "tri_state"))
      (node (ref "RS08") (pin "34") (pinfunction "34_34") (pintype "passive"))
    )
    (net (code "57") (name "DMA00") (class "Default")
      (node (ref "DMA0-3") (pin "7") (pinfunction "QD_7") (pintype "output"))
      (node (ref "IC38") (pin "8") (pinfunction "A4_8") (pintype "input"))
      (node (ref "RS08") (pin "16") (pinfunction "16_16") (pintype "passive"))
    )
    (net (code "58") (name "DMA01") (class "Default")
      (node (ref "DMA0-3") (pin "6") (pinfunction "QC_6") (pintype "output"))
      (node (ref "IC38") (pin "6") (pinfunction "A3_6") (pintype "input"))
      (node (ref "RS08") (pin "20") (pinfunction "20_20") (pintype "passive"))
    )
    (net (code "59") (name "DMA02") (class "Default")
      (node (ref "DMA0-3") (pin "2") (pinfunction "QB_2") (pintype "output"))
      (node (ref "IC38") (pin "4") (pinfunction "A2_4") (pintype "input"))
      (node (ref "RS08") (pin "14") (pinfunction "14_14") (pintype "passive"))
    )
    (net (code "60") (name "DMA03") (class "Default")
      (node (ref "DMA0-3") (pin "3") (pinfunction "QA_3") (pintype "output"))
      (node (ref "IC38") (pin "2") (pinfunction "A1_2") (pintype "input"))
      (node (ref "RS08") (pin "12") (pinfunction "12_12") (pintype "passive"))
    )
    (net (code "61") (name "DMA04") (class "Default")
      (node (ref "DMA4-7") (pin "7") (pinfunction "QD_7") (pintype "output"))
      (node (ref "IC24") (pin "17") (pinfunction "A4_17") (pintype "input"))
      (node (ref "RS08") (pin "9") (pinfunction "9_9") (pintype "passive"))
    )
    (net (code "62") (name "DMA05") (class "Default")
      (node (ref "DMA4-7") (pin "6") (pinfunction "QC_6") (pintype "output"))
      (node (ref "IC24") (pin "15") (pinfunction "A3_15") (pintype "input"))
      (node (ref "RS08") (pin "11") (pinfunction "11_11") (pintype "passive"))
    )
    (net (code "63") (name "DMA06") (class "Default")
      (node (ref "DMA4-7") (pin "2") (pinfunction "QB_2") (pintype "output"))
      (node (ref "IC24") (pin "13") (pinfunction "A2_13") (pintype "input"))
      (node (ref "RS08") (pin "13") (pinfunction "13_13") (pintype "passive"))
    )
    (net (code "64") (name "DMA07") (class "Default")
      (node (ref "DMA4-7") (pin "3") (pinfunction "QA_3") (pintype "output"))
      (node (ref "IC24") (pin "11") (pinfunction "A1_11") (pintype "input"))
      (node (ref "RS08") (pin "15") (pinfunction "15_15") (pintype "passive"))
    )
    (net (code "65") (name "DMA08") (class "Default")
      (node (ref "DMA8-11") (pin "7") (pinfunction "QD_7") (pintype "output"))
      (node (ref "IC24") (pin "8") (pinfunction "A4_8") (pintype "input"))
      (node (ref "RS08") (pin "17") (pinfunction "17_17") (pintype "passive"))
    )
    (net (code "66") (name "DMA09") (class "Default")
      (node (ref "DMA8-11") (pin "6") (pinfunction "QC_6") (pintype "output"))
      (node (ref "IC24") (pin "6") (pinfunction "A3_6") (pintype "input"))
      (node (ref "RS08") (pin "19") (pinfunction "19_19") (pintype "passive"))
    )
    (net (code "67") (name "DMA10") (class "Default")
      (node (ref "DMA8-11") (pin "2") (pinfunction "QB_2") (pintype "output"))
      (node (ref "IC24") (pin "4") (pinfunction "A2_4") (pintype "input"))
      (node (ref "RS08") (pin "21") (pinfunction "21_21") (pintype "passive"))
    )
    (net (code "68") (name "DMA11") (class "Default")
      (node (ref "DMA8-11") (pin "3") (pinfunction "QA_3") (pintype "output"))
      (node (ref "IC24") (pin "2") (pinfunction "A1_2") (pintype "input"))
      (node (ref "RS08") (pin "23") (pinfunction "23_23") (pintype "passive"))
    )
    (net (code "69") (name "DONE") (class "Default")
      (node (ref "IC11") (pin "9") (pinfunction "Q_9") (pintype "output"))
      (node (ref "IC40") (pin "2") (pinfunction "I1_2") (pintype "input"))
    )
    (net (code "70") (name "EIE") (class "Default")
      (node (ref "IC37") (pin "2") (pinfunction "A1_2") (pintype "input"))
      (node (ref "IC40") (pin "9") (pinfunction "I0_9") (pintype "input"))
      (node (ref "INTENB") (pin "6") (pinfunction "QC_6") (pintype "output"))
    )
    (net (code "71") (name "ERROR") (class "Default")
      (node (ref "IC12") (pin "6") (pinfunction "O_6") (pintype "output"))
      (node (ref "IC40") (pin "10") (pinfunction "I1_10") (pintype "input"))
      (node (ref "IC7") (pin "2") (pinfunction "A_2") (pintype "input"))
    )
    (net (code "72") (name "F.1") (class "Default")
      (node (ref "FIELD") (pin "3") (pinfunction "QA_3") (pintype "output"))
      (node (ref "IC20") (pin "11") (pinfunction "A1_11") (pintype "input"))
      (node (ref "IC30") (pin "8") (pinfunction "A4_8") (pintype "input"))
    )
    (net (code "73") (name "F.2") (class "Default")
      (node (ref "FIELD") (pin "2") (pinfunction "QB_2") (pintype "output"))
      (node (ref "IC20") (pin "13") (pinfunction "A2_13") (pintype "input"))
      (node (ref "IC30") (pin "11") (pinfunction "A1_11") (pintype "input"))
    )
    (net (code "74") (name "F.3") (class "Default")
      (node (ref "FIELD") (pin "6") (pinfunction "QC_6") (pintype "output"))
      (node (ref "IC20") (pin "15") (pinfunction "A3_15") (pintype "input"))
      (node (ref "IC30") (pin "13") (pinfunction "A2_13") (pintype "input"))
    )
    (net (code "75") (name "GND") (class "Default")
      (node (ref "C1") (pin "2") (pinfunction "2_2") (pintype "passive"))
      (node (ref "C35L") (pin "1") (pinfunction "1_1") (pintype "passive"))
      (node (ref "C35L") (pin "11") (pinfunction "11_11") (pintype "passive"))
      (node (ref "C35L") (pin "13") (pinfunction "13_13") (pintype "passive"))
      (node (ref "C35L") (pin "15") (pinfunction "15_15") (pintype "passive"))
      (node (ref "C35L") (pin "17") (pinfunction "17_17") (pintype "passive"))
      (node (ref "C35L") (pin "19") (pinfunction "19_19") (pintype "passive"))
      (node (ref "C35L") (pin "21") (pinfunction "21_21") (pintype "passive"))
      (node (ref "C35L") (pin "23") (pinfunction "23_23") (pintype "passive"))
      (node (ref "C35L") (pin "25") (pinfunction "25_25") (pintype "passive"))
      (node (ref "C35L") (pin "27") (pinfunction "27_27") (pintype "passive"))
      (node (ref "C35L") (pin "29") (pinfunction "29_29") (pintype "passive"))
      (node (ref "C35L") (pin "3") (pinfunction "3_3") (pintype "passive"))
      (node (ref "C35L") (pin "31") (pinfunction "31_31") (pintype "passive"))
      (node (ref "C35L") (pin "33") (pinfunction "33_33") (pintype "passive"))
      (node (ref "C35L") (pin "35") (pinfunction "35_35") (pintype "passive"))
      (node (ref "C35L") (pin "37") (pinfunction "37_37") (pintype "passive"))
      (node (ref "C35L") (pin "39") (pinfunction "39_39") (pintype "passive"))
      (node (ref "C35L") (pin "5") (pinfunction "5_5") (pintype "passive"))
      (node (ref "C35L") (pin "7") (pinfunction "7_7") (pintype "passive"))
      (node (ref "C35L") (pin "9") (pinfunction "9_9") (pintype "passive"))
      (node (ref "C36L") (pin "1") (pinfunction "1_1") (pintype "passive"))
      (node (ref "C36L") (pin "11") (pinfunction "11_11") (pintype "passive"))
      (node (ref "C36L") (pin "13") (pinfunction "13_13") (pintype "passive"))
      (node (ref "C36L") (pin "15") (pinfunction "15_15") (pintype "passive"))
      (node (ref "C36L") (pin "17") (pinfunction "17_17") (pintype "passive"))
      (node (ref "C36L") (pin "19") (pinfunction "19_19") (pintype "passive"))
      (node (ref "C36L") (pin "21") (pinfunction "21_21") (pintype "passive"))
      (node (ref "C36L") (pin "23") (pinfunction "23_23") (pintype "passive"))
      (node (ref "C36L") (pin "25") (pinfunction "25_25") (pintype "passive"))
      (node (ref "C36L") (pin "27") (pinfunction "27_27") (pintype "passive"))
      (node (ref "C36L") (pin "29") (pinfunction "29_29") (pintype "passive"))
      (node (ref "C36L") (pin "3") (pinfunction "3_3") (pintype "passive"))
      (node (ref "C36L") (pin "31") (pinfunction "31_31") (pintype "passive"))
      (node (ref "C36L") (pin "33") (pinfunction "33_33") (pintype "passive"))
      (node (ref "C36L") (pin "35") (pinfunction "35_35") (pintype "passive"))
      (node (ref "C36L") (pin "37") (pinfunction "37_37") (pintype "passive"))
      (node (ref "C36L") (pin "39") (pinfunction "39_39") (pintype "passive"))
      (node (ref "C36L") (pin "5") (pinfunction "5_5") (pintype "passive"))
      (node (ref "C36L") (pin "7") (pinfunction "7_7") (pintype "passive"))
      (node (ref "C36L") (pin "9") (pinfunction "9_9") (pintype "passive"))
      (node (ref "D34L") (pin "1") (pinfunction "1_1") (pintype "passive"))
      (node (ref "D34L") (pin "11") (pinfunction "11_11") (pintype "passive"))
      (node (ref "D34L") (pin "13") (pinfunction "13_13") (pintype "passive"))
      (node (ref "D34L") (pin "15") (pinfunction "15_15") (pintype "passive"))
      (node (ref "D34L") (pin "17") (pinfunction "17_17") (pintype "passive"))
      (node (ref "D34L") (pin "19") (pinfunction "19_19") (pintype "passive"))
      (node (ref "D34L") (pin "21") (pinfunction "21_21") (pintype "passive"))
      (node (ref "D34L") (pin "23") (pinfunction "23_23") (pintype "passive"))
      (node (ref "D34L") (pin "25") (pinfunction "25_25") (pintype "passive"))
      (node (ref "D34L") (pin "27") (pinfunction "27_27") (pintype "passive"))
      (node (ref "D34L") (pin "29") (pinfunction "29_29") (pintype "passive"))
      (node (ref "D34L") (pin "3") (pinfunction "3_3") (pintype "passive"))
      (node (ref "D34L") (pin "31") (pinfunction "31_31") (pintype "passive"))
      (node (ref "D34L") (pin "33") (pinfunction "33_33") (pintype "passive"))
      (node (ref "D34L") (pin "35") (pinfunction "35_35") (pintype "passive"))
      (node (ref "D34L") (pin "37") (pinfunction "37_37") (pintype "passive"))
      (node (ref "D34L") (pin "39") (pinfunction "39_39") (pintype "passive"))
      (node (ref "D34L") (pin "5") (pinfunction "5_5") (pintype "passive"))
      (node (ref "D34L") (pin "7") (pinfunction "7_7") (pintype "passive"))
      (node (ref "D34L") (pin "9") (pinfunction "9_9") (pintype "passive"))
      (node (ref "D35L") (pin "1") (pinfunction "1_1") (pintype "passive"))
      (node (ref "D35L") (pin "11") (pinfunction "11_11") (pintype "passive"))
      (node (ref "D35L") (pin "13") (pinfunction "13_13") (pintype "passive"))
      (node (ref "D35L") (pin "15") (pinfunction "15_15") (pintype "passive"))
      (node (ref "D35L") (pin "17") (pinfunction "17_17") (pintype "passive"))
      (node (ref "D35L") (pin "19") (pinfunction "19_19") (pintype "passive"))
      (node (ref "D35L") (pin "21") (pinfunction "21_21") (pintype "passive"))
      (node (ref "D35L") (pin "23") (pinfunction "23_23") (pintype "passive"))
      (node (ref "D35L") (pin "25") (pinfunction "25_25") (pintype "passive"))
      (node (ref "D35L") (pin "27") (pinfunction "27_27") (pintype "passive"))
      (node (ref "D35L") (pin "29") (pinfunction "29_29") (pintype "passive"))
      (node (ref "D35L") (pin "3") (pinfunction "3_3") (pintype "passive"))
      (node (ref "D35L") (pin "31") (pinfunction "31_31") (pintype "passive"))
      (node (ref "D35L") (pin "33") (pinfunction "33_33") (pintype "passive"))
      (node (ref "D35L") (pin "35") (pinfunction "35_35") (pintype "passive"))
      (node (ref "D35L") (pin "37") (pinfunction "37_37") (pintype "passive"))
      (node (ref "D35L") (pin "39") (pinfunction "39_39") (pintype "passive"))
      (node (ref "D35L") (pin "5") (pinfunction "5_5") (pintype "passive"))
      (node (ref "D35L") (pin "7") (pinfunction "7_7") (pintype "passive"))
      (node (ref "D35L") (pin "9") (pinfunction "9_9") (pintype "passive"))
      (node (ref "D36L") (pin "1") (pinfunction "1_1") (pintype "passive"))
      (node (ref "D36L") (pin "11") (pinfunction "11_11") (pintype "passive"))
      (node (ref "D36L") (pin "13") (pinfunction "13_13") (pintype "passive"))
      (node (ref "D36L") (pin "15") (pinfunction "15_15") (pintype "passive"))
      (node (ref "D36L") (pin "17") (pinfunction "17_17") (pintype "passive"))
      (node (ref "D36L") (pin "19") (pinfunction "19_19") (pintype "passive"))
      (node (ref "D36L") (pin "21") (pinfunction "21_21") (pintype "passive"))
      (node (ref "D36L") (pin "23") (pinfunction "23_23") (pintype "passive"))
      (node (ref "D36L") (pin "25") (pinfunction "25_25") (pintype "passive"))
      (node (ref "D36L") (pin "27") (pinfunction "27_27") (pintype "passive"))
      (node (ref "D36L") (pin "29") (pinfunction "29_29") (pintype "passive"))
      (node (ref "D36L") (pin "3") (pinfunction "3_3") (pintype "passive"))
      (node (ref "D36L") (pin "31") (pinfunction "31_31") (pintype "passive"))
      (node (ref "D36L") (pin "33") (pinfunction "33_33") (pintype "passive"))
      (node (ref "D36L") (pin "35") (pinfunction "35_35") (pintype "passive"))
      (node (ref "D36L") (pin "37") (pinfunction "37_37") (pintype "passive"))
      (node (ref "D36L") (pin "39") (pinfunction "39_39") (pintype "passive"))
      (node (ref "D36L") (pin "5") (pinfunction "5_5") (pintype "passive"))
      (node (ref "D36L") (pin "7") (pinfunction "7_7") (pintype "passive"))
      (node (ref "D36L") (pin "9") (pinfunction "9_9") (pintype "passive"))
      (node (ref "DAR4-7") (pin "4") (pinfunction "DN_4") (pintype "input"))
      (node (ref "DAR8-11") (pin "4") (pinfunction "DN_4") (pintype "input"))
      (node (ref "DMA0-3") (pin "4") (pinfunction "DN_4") (pintype "input"))
      (node (ref "DMA4-7") (pin "4") (pinfunction "DN_4") (pintype "input"))
      (node (ref "DMA8-11") (pin "4") (pinfunction "DN_4") (pintype "input"))
      (node (ref "FIELD") (pin "4") (pinfunction "DN_4") (pintype "input"))
      (node (ref "FIELD") (pin "5") (pinfunction "UP_5") (pintype "input"))
      (node (ref "FIELD") (pin "9") (pinfunction "D_9") (pintype "input"))
      (node (ref "IC1") (pin "7") (pinfunction "G_7") (pintype "input"))
      (node (ref "IC10") (pin "12") (pinfunction "D_12") (pintype "input"))
      (node (ref "IC10") (pin "2") (pinfunction "D_2") (pintype "input"))
      (node (ref "IC13") (pin "1") (pinfunction "G_1") (pintype "input"))
      (node (ref "IC13") (pin "2") (pinfunction "H_2") (pintype "input"))
      (node (ref "IC14") (pin "1") (pinfunction "G_1") (pintype "input"))
      (node (ref "IC14") (pin "13") (pinfunction "F_13") (pintype "input"))
      (node (ref "IC14") (pin "2") (pinfunction "H_2") (pintype "input"))
      (node (ref "IC14") (pin "4") (pinfunction "OI_4") (pintype "input"))
      (node (ref "IC15") (pin "4") (pinfunction "OI_4") (pintype "input"))
      (node (ref "IC16") (pin "1") (pinfunction "G_1") (pintype "input"))
      (node (ref "IC16") (pin "15") (pinfunction "G_15") (pintype "input"))
      (node (ref "IC17") (pin "1") (pinfunction "G_1") (pintype "input"))
      (node (ref "IC17") (pin "15") (pinfunction "G_15") (pintype "input"))
      (node (ref "IC2") (pin "7") (pinfunction "G_7") (pintype "input"))
      (node (ref "IC20") (pin "17") (pinfunction "A4_17") (pintype "input"))
      (node (ref "IC23") (pin "2") (pinfunction "D_2") (pintype "input"))
      (node (ref "IC25") (pin "5") (pinfunction "G2B_5") (pintype "input"))
      (node (ref "IC29") (pin "5") (pinfunction "G2B_5") (pintype "input"))
      (node (ref "IC3") (pin "7") (pinfunction "G_7") (pintype "input"))
      (node (ref "IC30") (pin "6") (pinfunction "A3_6") (pintype "input"))
      (node (ref "IC32") (pin "5") (pinfunction "G2B_5") (pintype "input"))
      (node (ref "IC35") (pin "13") (pinfunction "A2_13") (pintype "input"))
      (node (ref "IC35") (pin "15") (pinfunction "A3_15") (pintype "input"))
      (node (ref "IC35") (pin "17") (pinfunction "A4_17") (pintype "input"))
      (node (ref "IC36") (pin "4") (pinfunction "G2A_4") (pintype "input"))
      (node (ref "IC36") (pin "5") (pinfunction "G2B_5") (pintype "input"))
      (node (ref "IC37") (pin "6") (pinfunction "A3_6") (pintype "input"))
      (node (ref "IC38") (pin "11") (pinfunction "A1_11") (pintype "input"))
      (node (ref "IC38") (pin "13") (pinfunction "A2_13") (pintype "input"))
      (node (ref "IC38") (pin "15") (pinfunction "A3_15") (pintype "input"))
      (node (ref "IC38") (pin "17") (pinfunction "A4_17") (pintype "input"))
      (node (ref "IC4") (pin "7") (pinfunction "G_7") (pintype "input"))
      (node (ref "IC7") (pin "1") (pinfunction "G_1") (pintype "input"))
      (node (ref "IC7") (pin "15") (pinfunction "G_15") (pintype "input"))
      (node (ref "IC8") (pin "1") (pinfunction "GND_1") (pintype "power_in"))
      (node (ref "IC9") (pin "12") (pinfunction "D_12") (pintype "input"))
      (node (ref "IC9") (pin "2") (pinfunction "D_2") (pintype "input"))
      (node (ref "INTENB") (pin "4") (pinfunction "DN_4") (pintype "input"))
      (node (ref "INTENB") (pin "5") (pinfunction "UP_5") (pintype "input"))
      (node (ref "INTENB") (pin "9") (pinfunction "D_9") (pintype "input"))
      (node (ref "J10") (pin "2") (pinfunction "2_2") (pintype "passive"))
      (node (ref "J11") (pin "2") (pinfunction "2_2") (pintype "passive"))
      (node (ref "J12") (pin "2") (pinfunction "2_2") (pintype "passive"))
      (node (ref "J13") (pin "2") (pinfunction "2_2") (pintype "passive"))
      (node (ref "J14") (pin "2") (pinfunction "2_2") (pintype "passive"))
      (node (ref "J2") (pin "2") (pinfunction "2_2") (pintype "passive"))
      (node (ref "J6") (pin "2") (pinfunction "2_2") (pintype "passive"))
      (node (ref "J8") (pin "2") (pinfunction "2_2") (pintype "passive"))
      (node (ref "J9") (pin "2") (pinfunction "2_2") (pintype "passive"))
      (node (ref "RS08") (pin "31") (pinfunction "31_31") (pintype "passive"))
      (node (ref "RS08") (pin "39") (pinfunction "39_39") (pintype "passive"))
    )
    (net (code "76") (name "NXD") (class "Default")
      (node (ref "IC23") (pin "5") (pinfunction "Q_5") (pintype "output"))
      (node (ref "IC30") (pin "4") (pinfunction "A2_4") (pintype "input"))
    )
    (net (code "77") (name "Net-(DAR4-7A-CLR)") (class "Default")
      (node (ref "DAR4-7") (pin "14") (pinfunction "CLR_14") (pintype "input"))
      (node (ref "DAR8-11") (pin "14") (pinfunction "CLR_14") (pintype "input"))
      (node (ref "IC18") (pin "8") (pinfunction "O_8") (pintype "output"))
    )
    (net (code "78") (name "Net-(DAR4-7A-UP)") (class "Default")
      (node (ref "DAR4-7") (pin "5") (pinfunction "UP_5") (pintype "input"))
      (node (ref "DAR8-11") (pin "12") (pinfunction "CO_12") (pintype "output"))
    )
    (net (code "79") (name "Net-(DAR8-11A-UP)") (class "Default")
      (node (ref "DAR8-11") (pin "5") (pinfunction "UP_5") (pintype "input"))
      (node (ref "DMA0-3") (pin "12") (pinfunction "CO_12") (pintype "output"))
    )
    (net (code "80") (name "Net-(DMA0-3A-CLR)") (class "Default")
      (node (ref "DMA0-3") (pin "14") (pinfunction "CLR_14") (pintype "input"))
      (node (ref "DMA4-7") (pin "14") (pinfunction "CLR_14") (pintype "input"))
      (node (ref "DMA8-11") (pin "14") (pinfunction "CLR_14") (pintype "input"))
      (node (ref "IC18") (pin "6") (pinfunction "O_6") (pintype "output"))
    )
    (net (code "81") (name "Net-(DMA0-3A-UP)") (class "Default")
      (node (ref "DMA0-3") (pin "5") (pinfunction "UP_5") (pintype "input"))
      (node (ref "DMA4-7") (pin "12") (pinfunction "CO_12") (pintype "output"))
    )
    (net (code "82") (name "Net-(DMA4-7A-UP)") (class "Default")
      (node (ref "DMA4-7") (pin "5") (pinfunction "UP_5") (pintype "input"))
      (node (ref "DMA8-11") (pin "12") (pinfunction "CO_12") (pintype "output"))
    )
    (net (code "83") (name "Net-(IC1A-D0)") (class "Default")
      (node (ref "IC1") (pin "4") (pinfunction "D0_4") (pintype "input"))
      (node (ref "SW1") (pin "16") (pinfunction "16_16") (pintype "passive"))
    )
    (net (code "84") (name "Net-(IC1A-D1)") (class "Default")
      (node (ref "IC1") (pin "3") (pinfunction "D1_3") (pintype "input"))
      (node (ref "SW1") (pin "15") (pinfunction "15_15") (pintype "passive"))
    )
    (net (code "85") (name "Net-(IC1A-D2)") (class "Default")
      (node (ref "IC1") (pin "2") (pinfunction "D2_2") (pintype "input"))
      (node (ref "SW1") (pin "14") (pinfunction "14_14") (pintype "passive"))
    )
    (net (code "86") (name "Net-(IC1A-D3)") (class "Default")
      (node (ref "IC1") (pin "1") (pinfunction "D3_1") (pintype "input"))
      (node (ref "SW1") (pin "13") (pinfunction "13_13") (pintype "passive"))
    )
    (net (code "87") (name "Net-(IC1A-D4)") (class "Default")
      (node (ref "IC1") (pin "15") (pinfunction "D4_15") (pintype "input"))
      (node (ref "SW1") (pin "12") (pinfunction "12_12") (pintype "passive"))
    )
    (net (code "88") (name "Net-(IC1A-D5)") (class "Default")
      (node (ref "IC1") (pin "14") (pinfunction "D5_14") (pintype "input"))
      (node (ref "SW1") (pin "11") (pinfunction "11_11") (pintype "passive"))
    )
    (net (code "89") (name "Net-(IC1A-D6)") (class "Default")
      (node (ref "IC1") (pin "13") (pinfunction "D6_13") (pintype "input"))
      (node (ref "SW1") (pin "10") (pinfunction "10_10") (pintype "passive"))
    )
    (net (code "90") (name "Net-(IC1A-D7)") (class "Default")
      (node (ref "IC1") (pin "12") (pinfunction "D7_12") (pintype "input"))
      (node (ref "SW1") (pin "9") (pinfunction "9_9") (pintype "passive"))
    )
    (net (code "91") (name "Net-(IC1A-Y)") (class "Default")
      (node (ref "IC1") (pin "5") (pinfunction "Y_5") (pintype "output"))
      (node (ref "IC5") (pin "1") (pinfunction "I0_1") (pintype "input"))
    )
    (net (code "92") (name "Net-(IC2A-D0)") (class "Default")
      (node (ref "IC2") (pin "4") (pinfunction "D0_4") (pintype "input"))
      (node (ref "SW2") (pin "16") (pinfunction "16_16") (pintype "passive"))
    )
    (net (code "93") (name "Net-(IC2A-D1)") (class "Default")
      (node (ref "IC2") (pin "3") (pinfunction "D1_3") (pintype "input"))
      (node (ref "SW2") (pin "15") (pinfunction "15_15") (pintype "passive"))
    )
    (net (code "94") (name "Net-(IC2A-D2)") (class "Default")
      (node (ref "IC2") (pin "2") (pinfunction "D2_2") (pintype "input"))
      (node (ref "SW2") (pin "14") (pinfunction "14_14") (pintype "passive"))
    )
    (net (code "95") (name "Net-(IC2A-D3)") (class "Default")
      (node (ref "IC2") (pin "1") (pinfunction "D3_1") (pintype "input"))
      (node (ref "SW2") (pin "13") (pinfunction "13_13") (pintype "passive"))
    )
    (net (code "96") (name "Net-(IC2A-D4)") (class "Default")
      (node (ref "IC2") (pin "15") (pinfunction "D4_15") (pintype "input"))
      (node (ref "SW2") (pin "12") (pinfunction "12_12") (pintype "passive"))
    )
    (net (code "97") (name "Net-(IC2A-D5)") (class "Default")
      (node (ref "IC2") (pin "14") (pinfunction "D5_14") (pintype "input"))
      (node (ref "SW2") (pin "11") (pinfunction "11_11") (pintype "passive"))
    )
    (net (code "98") (name "Net-(IC2A-D6)") (class "Default")
      (node (ref "IC2") (pin "13") (pinfunction "D6_13") (pintype "input"))
      (node (ref "SW2") (pin "10") (pinfunction "10_10") (pintype "passive"))
    )
    (net (code "99") (name "Net-(IC2A-D7)") (class "Default")
      (node (ref "IC2") (pin "12") (pinfunction "D7_12") (pintype "input"))
      (node (ref "SW2") (pin "9") (pinfunction "9_9") (pintype "passive"))
    )
    (net (code "100") (name "Net-(IC2A-Y)") (class "Default")
      (node (ref "IC2") (pin "5") (pinfunction "Y_5") (pintype "output"))
      (node (ref "IC5") (pin "2") (pinfunction "I1_2") (pintype "input"))
    )
    (net (code "101") (name "Net-(IC3A-D0)") (class "Default")
      (node (ref "IC3") (pin "4") (pinfunction "D0_4") (pintype "input"))
      (node (ref "SW3") (pin "16") (pinfunction "16_16") (pintype "passive"))
    )
    (net (code "102") (name "Net-(IC3A-D1)") (class "Default")
      (node (ref "IC3") (pin "3") (pinfunction "D1_3") (pintype "input"))
      (node (ref "SW3") (pin "15") (pinfunction "15_15") (pintype "passive"))
    )
    (net (code "103") (name "Net-(IC3A-D2)") (class "Default")
      (node (ref "IC3") (pin "2") (pinfunction "D2_2") (pintype "input"))
      (node (ref "SW3") (pin "14") (pinfunction "14_14") (pintype "passive"))
    )
    (net (code "104") (name "Net-(IC3A-D3)") (class "Default")
      (node (ref "IC3") (pin "1") (pinfunction "D3_1") (pintype "input"))
      (node (ref "SW3") (pin "13") (pinfunction "13_13") (pintype "passive"))
    )
    (net (code "105") (name "Net-(IC3A-D4)") (class "Default")
      (node (ref "IC3") (pin "15") (pinfunction "D4_15") (pintype "input"))
      (node (ref "SW3") (pin "12") (pinfunction "12_12") (pintype "passive"))
    )
    (net (code "106") (name "Net-(IC3A-D5)") (class "Default")
      (node (ref "IC3") (pin "14") (pinfunction "D5_14") (pintype "input"))
      (node (ref "SW3") (pin "11") (pinfunction "11_11") (pintype "passive"))
    )
    (net (code "107") (name "Net-(IC3A-D6)") (class "Default")
      (node (ref "IC3") (pin "13") (pinfunction "D6_13") (pintype "input"))
      (node (ref "SW3") (pin "10") (pinfunction "10_10") (pintype "passive"))
    )
    (net (code "108") (name "Net-(IC3A-D7)") (class "Default")
      (node (ref "IC3") (pin "12") (pinfunction "D7_12") (pintype "input"))
      (node (ref "SW3") (pin "9") (pinfunction "9_9") (pintype "passive"))
    )
    (net (code "109") (name "Net-(IC3A-Y)") (class "Default")
      (node (ref "IC3") (pin "5") (pinfunction "Y_5") (pintype "output"))
      (node (ref "IC5") (pin "4") (pinfunction "I2_4") (pintype "input"))
    )
    (net (code "110") (name "Net-(IC4A-D0)") (class "Default")
      (node (ref "IC4") (pin "4") (pinfunction "D0_4") (pintype "input"))
      (node (ref "SW4") (pin "16") (pinfunction "16_16") (pintype "passive"))
    )
    (net (code "111") (name "Net-(IC4A-D1)") (class "Default")
      (node (ref "IC4") (pin "3") (pinfunction "D1_3") (pintype "input"))
      (node (ref "SW4") (pin "15") (pinfunction "15_15") (pintype "passive"))
    )
    (net (code "112") (name "Net-(IC4A-D2)") (class "Default")
      (node (ref "IC4") (pin "2") (pinfunction "D2_2") (pintype "input"))
      (node (ref "SW4") (pin "14") (pinfunction "14_14") (pintype "passive"))
    )
    (net (code "113") (name "Net-(IC4A-D3)") (class "Default")
      (node (ref "IC4") (pin "1") (pinfunction "D3_1") (pintype "input"))
      (node (ref "SW4") (pin "13") (pinfunction "13_13") (pintype "passive"))
    )
    (net (code "114") (name "Net-(IC4A-D4)") (class "Default")
      (node (ref "IC4") (pin "15") (pinfunction "D4_15") (pintype "input"))
      (node (ref "SW4") (pin "12") (pinfunction "12_12") (pintype "passive"))
    )
    (net (code "115") (name "Net-(IC4A-D5)") (class "Default")
      (node (ref "IC4") (pin "14") (pinfunction "D5_14") (pintype "input"))
      (node (ref "SW4") (pin "11") (pinfunction "11_11") (pintype "passive"))
    )
    (net (code "116") (name "Net-(IC4A-D6)") (class "Default")
      (node (ref "IC4") (pin "13") (pinfunction "D6_13") (pintype "input"))
      (node (ref "SW4") (pin "10") (pinfunction "10_10") (pintype "passive"))
    )
    (net (code "117") (name "Net-(IC4A-D7)") (class "Default")
      (node (ref "IC4") (pin "12") (pinfunction "D7_12") (pintype "input"))
      (node (ref "SW4") (pin "9") (pinfunction "9_9") (pintype "passive"))
    )
    (net (code "118") (name "Net-(IC4A-Y)") (class "Default")
      (node (ref "IC4") (pin "5") (pinfunction "Y_5") (pintype "output"))
      (node (ref "IC5") (pin "5") (pinfunction "I3_5") (pintype "input"))
    )
    (net (code "119") (name "Net-(IC8-CV)") (class "Default")
      (node (ref "C2") (pin "2") (pinfunction "2_2") (pintype "passive"))
      (node (ref "IC8") (pin "5") (pinfunction "CV_5") (pintype "input"))
    )
    (net (code "120") (name "Net-(IC8-DIS)") (class "Default")
      (node (ref "IC8") (pin "7") (pinfunction "DIS_7") (pintype "input"))
      (node (ref "RA") (pin "2") (pinfunction "2_2") (pintype "passive"))
      (node (ref "RB") (pin "1") (pinfunction "1_1") (pintype "passive"))
    )
    (net (code "121") (name "Net-(IC8-THR)") (class "Default")
      (node (ref "C1") (pin "1") (pinfunction "1_1") (pintype "passive"))
      (node (ref "IC8") (pin "2") (pinfunction "TR_2") (pintype "input"))
      (node (ref "IC8") (pin "6") (pinfunction "THR_6") (pintype "input"))
      (node (ref "RB") (pin "2") (pinfunction "2_2") (pintype "passive"))
    )
    (net (code "122") (name "Net-(IC10B-PRE)") (class "Default")
      (node (ref "IC10") (pin "10") (pinfunction "PRE_10") (pintype "input"))
      (node (ref "IC18") (pin "11") (pinfunction "O_11") (pintype "output"))
    )
    (net (code "123") (name "Net-(IC10B-~{Q})") (class "Default")
      (node (ref "IC10") (pin "8") (pinfunction "~{Q}_8") (pintype "output"))
      (node (ref "IC11") (pin "11") (pinfunction "CLK_11") (pintype "input"))
    )
    (net (code "124") (name "Net-(IC12A-I0)") (class "Default")
      (node (ref "IC12") (pin "1") (pinfunction "I0_1") (pintype "input"))
      (node (ref "IC12") (pin "2") (pinfunction "I1_2") (pintype "input"))
      (node (ref "IC8") (pin "3") (pinfunction "Q_3") (pintype "output"))
      (node (ref "RL") (pin "2") (pinfunction "2_2") (pintype "passive"))
    )
    (net (code "125") (name "Net-(IC12B-I1)") (class "Default")
      (node (ref "IC12") (pin "5") (pinfunction "I1_5") (pintype "input"))
      (node (ref "IC12") (pin "8") (pinfunction "O_8") (pintype "output"))
    )
    (net (code "126") (name "Net-(IC12C-I0)") (class "Default")
      (node (ref "IC12") (pin "10") (pinfunction "I1_10") (pintype "input"))
      (node (ref "IC12") (pin "11") (pinfunction "O_11") (pintype "output"))
      (node (ref "IC12") (pin "9") (pinfunction "I0_9") (pintype "input"))
    )
    (net (code "127") (name "Net-(IC13A-A)") (class "Default")
      (node (ref "IC13") (pin "8") (pinfunction "A_8") (pintype "input"))
      (node (ref "IC14") (pin "8") (pinfunction "A_8") (pintype "input"))
      (node (ref "IC15") (pin "6") (pinfunction "ODD_6") (pintype "output"))
    )
    (net (code "128") (name "Net-(IC16B-Y1)") (class "Default")
      (node (ref "IC16") (pin "11") (pinfunction "Y1_11") (pintype "output"))
      (node (ref "IC22") (pin "1") (pinfunction "I_1") (pintype "input"))
    )
    (net (code "129") (name "Net-(IC17A-Y0)") (class "Default")
      (node (ref "IC17") (pin "4") (pinfunction "Y0_4") (pintype "output"))
      (node (ref "IC22") (pin "11") (pinfunction "I_11") (pintype "input"))
    )
    (net (code "130") (name "Net-(IC19A-I)") (class "Default")
      (node (ref "IC19") (pin "1") (pinfunction "I_1") (pintype "input"))
      (node (ref "IC7") (pin "5") (pinfunction "Y1_5") (pintype "output"))
    )
    (net (code "131") (name "Net-(IC19E-I)") (class "Default")
      (node (ref "IC19") (pin "11") (pinfunction "I_11") (pintype "input"))
      (node (ref "IC7") (pin "12") (pinfunction "Y0_12") (pintype "output"))
    )
    (net (code "132") (name "Net-(IC21A-Y0)") (class "Default")
      (node (ref "IC21") (pin "4") (pinfunction "Y0_4") (pintype "output"))
      (node (ref "SW1") (pin "1") (pinfunction "1_1") (pintype "passive"))
      (node (ref "SW1") (pin "2") (pinfunction "2_2") (pintype "passive"))
      (node (ref "SW1") (pin "3") (pinfunction "3_3") (pintype "passive"))
      (node (ref "SW1") (pin "4") (pinfunction "4_4") (pintype "passive"))
      (node (ref "SW1") (pin "5") (pinfunction "5_5") (pintype "passive"))
      (node (ref "SW1") (pin "6") (pinfunction "6_6") (pintype "passive"))
      (node (ref "SW1") (pin "7") (pinfunction "7_7") (pintype "passive"))
      (node (ref "SW1") (pin "8") (pinfunction "8_8") (pintype "passive"))
    )
    (net (code "133") (name "Net-(IC21A-Y1)") (class "Default")
      (node (ref "IC21") (pin "5") (pinfunction "Y1_5") (pintype "output"))
      (node (ref "SW2") (pin "1") (pinfunction "1_1") (pintype "passive"))
      (node (ref "SW2") (pin "2") (pinfunction "2_2") (pintype "passive"))
      (node (ref "SW2") (pin "3") (pinfunction "3_3") (pintype "passive"))
      (node (ref "SW2") (pin "4") (pinfunction "4_4") (pintype "passive"))
      (node (ref "SW2") (pin "5") (pinfunction "5_5") (pintype "passive"))
      (node (ref "SW2") (pin "6") (pinfunction "6_6") (pintype "passive"))
      (node (ref "SW2") (pin "7") (pinfunction "7_7") (pintype "passive"))
      (node (ref "SW2") (pin "8") (pinfunction "8_8") (pintype "passive"))
    )
    (net (code "134") (name "Net-(IC21A-Y2)") (class "Default")
      (node (ref "IC21") (pin "6") (pinfunction "Y2_6") (pintype "output"))
      (node (ref "SW3") (pin "1") (pinfunction "1_1") (pintype "passive"))
      (node (ref "SW3") (pin "2") (pinfunction "2_2") (pintype "passive"))
      (node (ref "SW3") (pin "3") (pinfunction "3_3") (pintype "passive"))
      (node (ref "SW3") (pin "4") (pinfunction "4_4") (pintype "passive"))
      (node (ref "SW3") (pin "5") (pinfunction "5_5") (pintype "passive"))
      (node (ref "SW3") (pin "6") (pinfunction "6_6") (pintype "passive"))
      (node (ref "SW3") (pin "7") (pinfunction "7_7") (pintype "passive"))
      (node (ref "SW3") (pin "8") (pinfunction "8_8") (pintype "passive"))
    )
    (net (code "135") (name "Net-(IC21A-Y3)") (class "Default")
      (node (ref "IC21") (pin "7") (pinfunction "Y3_7") (pintype "output"))
      (node (ref "SW4") (pin "1") (pinfunction "1_1") (pintype "passive"))
      (node (ref "SW4") (pin "2") (pinfunction "2_2") (pintype "passive"))
      (node (ref "SW4") (pin "3") (pinfunction "3_3") (pintype "passive"))
      (node (ref "SW4") (pin "4") (pinfunction "4_4") (pintype "passive"))
      (node (ref "SW4") (pin "5") (pinfunction "5_5") (pintype "passive"))
      (node (ref "SW4") (pin "6") (pinfunction "6_6") (pintype "passive"))
      (node (ref "SW4") (pin "7") (pinfunction "7_7") (pintype "passive"))
      (node (ref "SW4") (pin "8") (pinfunction "8_8") (pintype "passive"))
    )
    (net (code "136") (name "Net-(IC36A-Y0)") (class "Default")
      (node (ref "IC36") (pin "15") (pinfunction "Y0_15") (pintype "output"))
      (node (ref "PAD2") (pin "1") (pinfunction "P_1") (pintype "passive"))
    )
    (net (code "137") (name "Net-(IC36A-Y1)") (class "Default")
      (node (ref "IC36") (pin "14") (pinfunction "Y1_14") (pintype "output"))
      (node (ref "PAD3") (pin "1") (pinfunction "P_1") (pintype "passive"))
    )
    (net (code "138") (name "Net-(IC36A-Y2)") (class "Default")
      (node (ref "IC36") (pin "13") (pinfunction "Y2_13") (pintype "output"))
      (node (ref "PAD4") (pin "1") (pinfunction "P_1") (pintype "passive"))
    )
    (net (code "139") (name "Net-(IC36A-Y3)") (class "Default")
      (node (ref "IC36") (pin "12") (pinfunction "Y3_12") (pintype "output"))
      (node (ref "PAD5") (pin "1") (pinfunction "P_1") (pintype "passive"))
    )
    (net (code "140") (name "Net-(IC36A-Y4)") (class "Default")
      (node (ref "IC36") (pin "11") (pinfunction "Y4_11") (pintype "output"))
      (node (ref "PAD6") (pin "1") (pinfunction "P_1") (pintype "passive"))
    )
    (net (code "141") (name "Net-(IC36A-Y5)") (class "Default")
      (node (ref "IC36") (pin "10") (pinfunction "Y5_10") (pintype "output"))
      (node (ref "PAD7") (pin "1") (pinfunction "P_1") (pintype "passive"))
    )
    (net (code "142") (name "Net-(IC36A-Y6)") (class "Default")
      (node (ref "IC36") (pin "9") (pinfunction "Y6_9") (pintype "output"))
      (node (ref "PAD8") (pin "1") (pinfunction "P_1") (pintype "passive"))
    )
    (net (code "143") (name "Net-(IC36A-Y7)") (class "Default")
      (node (ref "IC36") (pin "7") (pinfunction "Y7_7") (pintype "output"))
      (node (ref "PAD9") (pin "1") (pinfunction "P_1") (pintype "passive"))
    )
    (net (code "144") (name "PBIT") (class "Default")
      (node (ref "IC14") (pin "6") (pinfunction "ODD_6") (pintype "output"))
      (node (ref "IC35") (pin "11") (pinfunction "A1_11") (pintype "input"))
    )
    (net (code "145") (name "PCA") (class "Default")
      (node (ref "IC12") (pin "3") (pinfunction "O_3") (pintype "output"))
      (node (ref "IC37") (pin "8") (pinfunction "A4_8") (pintype "input"))
      (node (ref "IC40") (pin "5") (pinfunction "I1_5") (pintype "input"))
    )
    (net (code "146") (name "PER") (class "Default")
      (node (ref "IC30") (pin "2") (pinfunction "A1_2") (pintype "input"))
      (node (ref "IC9") (pin "9") (pinfunction "Q_9") (pintype "output"))
    )
    (net (code "147") (name "PIE") (class "Default")
      (node (ref "IC30") (pin "17") (pinfunction "A4_17") (pintype "input"))
      (node (ref "IC40") (pin "4") (pinfunction "I0_4") (pintype "input"))
      (node (ref "INTENB") (pin "2") (pinfunction "QB_2") (pintype "output"))
    )
    (net (code "148") (name "PROTECT") (class "Default")
      (node (ref "IC5") (pin "6") (pinfunction "O_6") (pintype "output"))
      (node (ref "IC6") (pin "3") (pinfunction "B_3") (pintype "input"))
    )
    (net (code "149") (name "VCC") (class "Default")
      (node (ref "C2") (pin "1") (pinfunction "1_1") (pintype "passive"))
      (node (ref "IC11") (pin "10") (pinfunction "PRE_10") (pintype "input"))
      (node (ref "IC11") (pin "4") (pinfunction "PRE_4") (pintype "input"))
      (node (ref "IC13") (pin "3") (pinfunction "EI_3") (pintype "input"))
      (node (ref "IC14") (pin "3") (pinfunction "EI_3") (pintype "input"))
      (node (ref "IC15") (pin "3") (pinfunction "EI_3") (pintype "input"))
      (node (ref "IC36") (pin "6") (pinfunction "G1_6") (pintype "input"))
      (node (ref "IC8") (pin "4") (pinfunction "R_4") (pintype "input"))
      (node (ref "IC8") (pin "8") (pinfunction "V+_8") (pintype "power_in"))
      (node (ref "J3") (pin "2") (pinfunction "2_2") (pintype "passive"))
      (node (ref "J4") (pin "2") (pinfunction "2_2") (pintype "passive"))
      (node (ref "J5") (pin "2") (pinfunction "2_2") (pintype "passive"))
      (node (ref "J7") (pin "2") (pinfunction "2_2") (pintype "passive"))
      (node (ref "R1") (pin "2") (pinfunction "2_2") (pintype "passive"))
      (node (ref "R2") (pin "2") (pinfunction "2_2") (pintype "passive"))
      (node (ref "RA") (pin "1") (pinfunction "1_1") (pintype "passive"))
      (node (ref "RL") (pin "1") (pinfunction "1_1") (pintype "passive"))
      (node (ref "RS08") (pin "2") (pinfunction "2_2") (pintype "passive"))
    )
    (net (code "150") (name "WLS") (class "Default")
      (node (ref "IC37") (pin "4") (pinfunction "A2_4") (pintype "input"))
      (node (ref "IC9") (pin "5") (pinfunction "Q_5") (pintype "output"))
    )
    (net (code "151") (name "WRITING") (class "Default")
      (node (ref "IC10") (pin "5") (pinfunction "Q_5") (pintype "output"))
      (node (ref "IC41") (pin "13") (pinfunction "B_13") (pintype "input"))
      (node (ref "IC41") (pin "14") (pinfunction "A_14") (pintype "input"))
      (node (ref "IC6") (pin "2") (pinfunction "A_2") (pintype "input"))
      (node (ref "RS08") (pin "18") (pinfunction "18_18") (pintype "passive"))
    )
    (net (code "152") (name "unconnected-(C35L-Pad20)") (class "Default")
      (node (ref "C35L") (pin "20") (pinfunction "20_20") (pintype "passive"))
    )
    (net (code "153") (name "unconnected-(C35L-Pad40)") (class "Default")
      (node (ref "C35L") (pin "40") (pinfunction "40_40") (pintype "passive"))
    )
    (net (code "154") (name "unconnected-(C36L-Pad20)") (class "Default")
      (node (ref "C36L") (pin "20") (pinfunction "20_20") (pintype "passive"))
    )
    (net (code "155") (name "unconnected-(C36L-Pad40)") (class "Default")
      (node (ref "C36L") (pin "40") (pinfunction "40_40") (pintype "passive"))
    )
    (net (code "156") (name "unconnected-(D34L-Pad20)") (class "Default")
      (node (ref "D34L") (pin "20") (pinfunction "20_20") (pintype "passive"))
    )
    (net (code "157") (name "unconnected-(D34L-Pad36)") (class "Default")
      (node (ref "D34L") (pin "36") (pinfunction "36_36") (pintype "passive"))
    )
    (net (code "158") (name "unconnected-(D34L-Pad38)") (class "Default")
      (node (ref "D34L") (pin "38") (pinfunction "38_38") (pintype "passive"))
    )
    (net (code "159") (name "unconnected-(D34L-Pad40)") (class "Default")
      (node (ref "D34L") (pin "40") (pinfunction "40_40") (pintype "passive"))
    )
    (net (code "160") (name "unconnected-(D35L-Pad20)") (class "Default")
      (node (ref "D35L") (pin "20") (pinfunction "20_20") (pintype "passive"))
    )
    (net (code "161") (name "unconnected-(D35L-Pad40)") (class "Default")
      (node (ref "D35L") (pin "40") (pinfunction "40_40") (pintype "passive"))
    )
    (net (code "162") (name "unconnected-(D36L-Pad20)") (class "Default")
      (node (ref "D36L") (pin "20") (pinfunction "20_20") (pintype "passive"))
    )
    (net (code "163") (name "unconnected-(D36L-Pad40)") (class "Default")
      (node (ref "D36L") (pin "40") (pinfunction "40_40") (pintype "passive"))
    )
    (net (code "164") (name "unconnected-(DAR4-7A-BO-Pad13)") (class "Default")
      (node (ref "DAR4-7") (pin "13") (pinfunction "BO_13") (pintype "output"))
    )
    (net (code "165") (name "unconnected-(DAR4-7A-CO-Pad12)") (class "Default")
      (node (ref "DAR4-7") (pin "12") (pinfunction "CO_12") (pintype "output"))
    )
    (net (code "166") (name "unconnected-(DAR8-11A-BO-Pad13)") (class "Default")
      (node (ref "DAR8-11") (pin "13") (pinfunction "BO_13") (pintype "output"))
    )
    (net (code "167") (name "unconnected-(DMA0-3A-BO-Pad13)") (class "Default")
      (node (ref "DMA0-3") (pin "13") (pinfunction "BO_13") (pintype "output"))
    )
    (net (code "168") (name "unconnected-(DMA4-7A-BO-Pad13)") (class "Default")
      (node (ref "DMA4-7") (pin "13") (pinfunction "BO_13") (pintype "output"))
    )
    (net (code "169") (name "unconnected-(DMA8-11A-BO-Pad13)") (class "Default")
      (node (ref "DMA8-11") (pin "13") (pinfunction "BO_13") (pintype "output"))
    )
    (net (code "170") (name "unconnected-(FIELDA-BO-Pad13)") (class "Default")
      (node (ref "FIELD") (pin "13") (pinfunction "BO_13") (pintype "output"))
    )
    (net (code "171") (name "unconnected-(FIELDA-CO-Pad12)") (class "Default")
      (node (ref "FIELD") (pin "12") (pinfunction "CO_12") (pintype "output"))
    )
    (net (code "172") (name "unconnected-(FIELDA-QD-Pad7)") (class "Default")
      (node (ref "FIELD") (pin "7") (pinfunction "QD_7") (pintype "output"))
    )
    (net (code "173") (name "unconnected-(IC1A-W-Pad6)") (class "Default")
      (node (ref "IC1") (pin "6") (pinfunction "W_6") (pintype "output"))
    )
    (net (code "174") (name "unconnected-(IC2A-W-Pad6)") (class "Default")
      (node (ref "IC2") (pin "6") (pinfunction "W_6") (pintype "output"))
    )
    (net (code "175") (name "unconnected-(IC3A-W-Pad6)") (class "Default")
      (node (ref "IC3") (pin "6") (pinfunction "W_6") (pintype "output"))
    )
    (net (code "176") (name "unconnected-(IC4A-W-Pad6)") (class "Default")
      (node (ref "IC4") (pin "6") (pinfunction "W_6") (pintype "output"))
    )
    (net (code "177") (name "unconnected-(IC6A-Y0-Pad4)") (class "Default")
      (node (ref "IC6") (pin "4") (pinfunction "Y0_4") (pintype "output"))
    )
    (net (code "178") (name "unconnected-(IC6A-Y2-Pad6)") (class "Default")
      (node (ref "IC6") (pin "6") (pinfunction "Y2_6") (pintype "output"))
    )
    (net (code "179") (name "unconnected-(IC7A-Y0-Pad4)") (class "Default")
      (node (ref "IC7") (pin "4") (pinfunction "Y0_4") (pintype "output"))
    )
    (net (code "180") (name "unconnected-(IC7A-Y2-Pad6)") (class "Default")
      (node (ref "IC7") (pin "6") (pinfunction "Y2_6") (pintype "output"))
    )
    (net (code "181") (name "unconnected-(IC7A-Y3-Pad7)") (class "Default")
      (node (ref "IC7") (pin "7") (pinfunction "Y3_7") (pintype "output"))
    )
    (net (code "182") (name "unconnected-(IC7B-Y1-Pad11)") (class "Default")
      (node (ref "IC7") (pin "11") (pinfunction "Y1_11") (pintype "output"))
    )
    (net (code "183") (name "unconnected-(IC7B-Y2-Pad10)") (class "Default")
      (node (ref "IC7") (pin "10") (pinfunction "Y2_10") (pintype "output"))
    )
    (net (code "184") (name "unconnected-(IC7B-Y3-Pad9)") (class "Default")
      (node (ref "IC7") (pin "9") (pinfunction "Y3_9") (pintype "output"))
    )
    (net (code "185") (name "unconnected-(IC10A-~{Q}-Pad6)") (class "Default")
      (node (ref "IC10") (pin "6") (pinfunction "~{Q}_6") (pintype "output"))
    )
    (net (code "186") (name "unconnected-(IC11A-Q-Pad5)") (class "Default")
      (node (ref "IC11") (pin "5") (pinfunction "Q_5") (pintype "output"))
    )
    (net (code "187") (name "unconnected-(IC11B-~{Q}-Pad8)") (class "Default")
      (node (ref "IC11") (pin "8") (pinfunction "~{Q}_8") (pintype "output"))
    )
    (net (code "188") (name "unconnected-(IC13A-ODD-Pad6)") (class "Default")
      (node (ref "IC13") (pin "6") (pinfunction "ODD_6") (pintype "output"))
    )
    (net (code "189") (name "unconnected-(IC14A-EVN-Pad5)") (class "Default")
      (node (ref "IC14") (pin "5") (pinfunction "EVN_5") (pintype "output"))
    )
    (net (code "190") (name "unconnected-(IC15A-EVN-Pad5)") (class "Default")
      (node (ref "IC15") (pin "5") (pinfunction "EVN_5") (pintype "output"))
    )
    (net (code "191") (name "unconnected-(IC16A-Y1-Pad5)") (class "Default")
      (node (ref "IC16") (pin "5") (pinfunction "Y1_5") (pintype "output"))
    )
    (net (code "192") (name "unconnected-(IC16A-Y2-Pad6)") (class "Default")
      (node (ref "IC16") (pin "6") (pinfunction "Y2_6") (pintype "output"))
    )
    (net (code "193") (name "unconnected-(IC16A-Y3-Pad7)") (class "Default")
      (node (ref "IC16") (pin "7") (pinfunction "Y3_7") (pintype "output"))
    )
    (net (code "194") (name "unconnected-(IC16B-Y2-Pad10)") (class "Default")
      (node (ref "IC16") (pin "10") (pinfunction "Y2_10") (pintype "output"))
    )
    (net (code "195") (name "unconnected-(IC16B-Y3-Pad9)") (class "Default")
      (node (ref "IC16") (pin "9") (pinfunction "Y3_9") (pintype "output"))
    )
    (net (code "196") (name "unconnected-(IC17A-Y1-Pad5)") (class "Default")
      (node (ref "IC17") (pin "5") (pinfunction "Y1_5") (pintype "output"))
    )
    (net (code "197") (name "unconnected-(IC17A-Y2-Pad6)") (class "Default")
      (node (ref "IC17") (pin "6") (pinfunction "Y2_6") (pintype "output"))
    )
    (net (code "198") (name "unconnected-(IC17A-Y3-Pad7)") (class "Default")
      (node (ref "IC17") (pin "7") (pinfunction "Y3_7") (pintype "output"))
    )
    (net (code "199") (name "unconnected-(IC17B-Y2-Pad10)") (class "Default")
      (node (ref "IC17") (pin "10") (pinfunction "Y2_10") (pintype "output"))
    )
    (net (code "200") (name "unconnected-(IC17B-Y3-Pad9)") (class "Default")
      (node (ref "IC17") (pin "9") (pinfunction "Y3_9") (pintype "output"))
    )
    (net (code "201") (name "unconnected-(IC20B-Y4-Pad3)") (class "Default")
      (node (ref "IC20") (pin "3") (pinfunction "Y4_3") (pintype "tri_state"))
    )
    (net (code "202") (name "unconnected-(IC21B-Y0-Pad12)") (class "Default")
      (node (ref "IC21") (pin "12") (pinfunction "Y0_12") (pintype "output"))
    )
    (net (code "203") (name "unconnected-(IC21B-Y1-Pad11)") (class "Default")
      (node (ref "IC21") (pin "11") (pinfunction "Y1_11") (pintype "output"))
    )
    (net (code "204") (name "unconnected-(IC21B-Y2-Pad10)") (class "Default")
      (node (ref "IC21") (pin "10") (pinfunction "Y2_10") (pintype "output"))
    )
    (net (code "205") (name "unconnected-(IC25A-Y3-Pad12)") (class "Default")
      (node (ref "IC25") (pin "12") (pinfunction "Y3_12") (pintype "output"))
    )
    (net (code "206") (name "unconnected-(IC25A-Y5-Pad10)") (class "Default")
      (node (ref "IC25") (pin "10") (pinfunction "Y5_10") (pintype "output"))
    )
    (net (code "207") (name "unconnected-(IC25A-Y6-Pad9)") (class "Default")
      (node (ref "IC25") (pin "9") (pinfunction "Y6_9") (pintype "output"))
    )
    (net (code "208") (name "unconnected-(IC25A-Y7-Pad7)") (class "Default")
      (node (ref "IC25") (pin "7") (pinfunction "Y7_7") (pintype "output"))
    )
    (net (code "209") (name "unconnected-(IC29A-Y3-Pad12)") (class "Default")
      (node (ref "IC29") (pin "12") (pinfunction "Y3_12") (pintype "output"))
    )
    (net (code "210") (name "unconnected-(IC29A-Y5-Pad10)") (class "Default")
      (node (ref "IC29") (pin "10") (pinfunction "Y5_10") (pintype "output"))
    )
    (net (code "211") (name "unconnected-(IC29A-Y6-Pad9)") (class "Default")
      (node (ref "IC29") (pin "9") (pinfunction "Y6_9") (pintype "output"))
    )
    (net (code "212") (name "unconnected-(IC29A-Y7-Pad7)") (class "Default")
      (node (ref "IC29") (pin "7") (pinfunction "Y7_7") (pintype "output"))
    )
    (net (code "213") (name "unconnected-(IC32A-Y3-Pad12)") (class "Default")
      (node (ref "IC32") (pin "12") (pinfunction "Y3_12") (pintype "output"))
    )
    (net (code "214") (name "unconnected-(IC32A-Y5-Pad10)") (class "Default")
      (node (ref "IC32") (pin "10") (pinfunction "Y5_10") (pintype "output"))
    )
    (net (code "215") (name "unconnected-(IC32A-Y6-Pad9)") (class "Default")
      (node (ref "IC32") (pin "9") (pinfunction "Y6_9") (pintype "output"))
    )
    (net (code "216") (name "unconnected-(IC32A-Y7-Pad7)") (class "Default")
      (node (ref "IC32") (pin "7") (pinfunction "Y7_7") (pintype "output"))
    )
    (net (code "217") (name "unconnected-(IC35B-Y2-Pad7)") (class "Default")
      (node (ref "IC35") (pin "7") (pinfunction "Y2_7") (pintype "tri_state"))
    )
    (net (code "218") (name "unconnected-(IC35B-Y3-Pad5)") (class "Default")
      (node (ref "IC35") (pin "5") (pinfunction "Y3_5") (pintype "tri_state"))
    )
    (net (code "219") (name "unconnected-(IC35B-Y4-Pad3)") (class "Default")
      (node (ref "IC35") (pin "3") (pinfunction "Y4_3") (pintype "tri_state"))
    )
    (net (code "220") (name "unconnected-(IC41A-Y1-Pad5)") (class "Default")
      (node (ref "IC41") (pin "5") (pinfunction "Y1_5") (pintype "output"))
    )
    (net (code "221") (name "unconnected-(IC41A-Y2-Pad6)") (class "Default")
      (node (ref "IC41") (pin "6") (pinfunction "Y2_6") (pintype "output"))
    )
    (net (code "222") (name "unconnected-(IC41B-Y1-Pad11)") (class "Default")
      (node (ref "IC41") (pin "11") (pinfunction "Y1_11") (pintype "output"))
    )
    (net (code "223") (name "unconnected-(IC41B-Y2-Pad10)") (class "Default")
      (node (ref "IC41") (pin "10") (pinfunction "Y2_10") (pintype "output"))
    )
    (net (code "224") (name "unconnected-(INTENBA-BO-Pad13)") (class "Default")
      (node (ref "INTENB") (pin "13") (pinfunction "BO_13") (pintype "output"))
    )
    (net (code "225") (name "unconnected-(INTENBA-CO-Pad12)") (class "Default")
      (node (ref "INTENB") (pin "12") (pinfunction "CO_12") (pintype "output"))
    )
    (net (code "226") (name "unconnected-(INTENBA-QD-Pad7)") (class "Default")
      (node (ref "INTENB") (pin "7") (pinfunction "QD_7") (pintype "output"))
    )
    (net (code "227") (name "~{3CYC}") (class "Default")
      (node (ref "C35L") (pin "28") (pinfunction "28_28") (pintype "passive"))
      (node (ref "J2") (pin "1") (pinfunction "1_1") (pintype "passive"))
    )
    (net (code "228") (name "~{601}") (class "Default")
      (node (ref "IC11") (pin "13") (pinfunction "CLR_13") (pintype "input"))
      (node (ref "IC18") (pin "4") (pinfunction "I0_4") (pintype "input"))
      (node (ref "IC18") (pin "5") (pinfunction "I1_5") (pintype "input"))
      (node (ref "IC23") (pin "1") (pinfunction "CLR_1") (pintype "input"))
      (node (ref "IC32") (pin "15") (pinfunction "Y0_15") (pintype "output"))
      (node (ref "IC9") (pin "1") (pinfunction "CLR_1") (pintype "input"))
      (node (ref "IC9") (pin "13") (pinfunction "CLR_13") (pintype "input"))
    )
    (net (code "229") (name "~{602}") (class "Default")
      (node (ref "IC10") (pin "1") (pinfunction "CLR_1") (pintype "input"))
      (node (ref "IC18") (pin "1") (pinfunction "I0_1") (pintype "input"))
      (node (ref "IC18") (pin "12") (pinfunction "I0_12") (pintype "input"))
      (node (ref "IC29") (pin "15") (pinfunction "Y0_15") (pintype "output"))
    )
    (net (code "230") (name "~{604}") (class "Default")
      (node (ref "IC10") (pin "4") (pinfunction "PRE_4") (pintype "input"))
      (node (ref "IC18") (pin "13") (pinfunction "I1_13") (pintype "input"))
      (node (ref "IC18") (pin "2") (pinfunction "I1_2") (pintype "input"))
      (node (ref "IC25") (pin "15") (pinfunction "Y0_15") (pintype "output"))
    )
    (net (code "231") (name "~{611}") (class "Default")
      (node (ref "FIELD") (pin "14") (pinfunction "CLR_14") (pintype "input"))
      (node (ref "IC32") (pin "14") (pinfunction "Y1_14") (pintype "output"))
      (node (ref "INTENB") (pin "14") (pinfunction "CLR_14") (pintype "input"))
    )
    (net (code "232") (name "~{612}") (class "Default")
      (node (ref "IC19") (pin "5") (pinfunction "I_5") (pintype "input"))
      (node (ref "IC29") (pin "14") (pinfunction "Y1_14") (pintype "output"))
    )
    (net (code "233") (name "~{614}") (class "Default")
      (node (ref "IC17") (pin "13") (pinfunction "B_13") (pintype "input"))
      (node (ref "IC22") (pin "3") (pinfunction "I_3") (pintype "input"))
      (node (ref "IC25") (pin "14") (pinfunction "Y1_14") (pintype "output"))
    )
    (net (code "234") (name "~{621}") (class "Default")
      (node (ref "IC32") (pin "13") (pinfunction "Y2_13") (pintype "output"))
      (node (ref "IC7") (pin "3") (pinfunction "B_3") (pintype "input"))
    )
    (net (code "235") (name "~{622}") (class "Default")
      (node (ref "IC29") (pin "13") (pinfunction "Y2_13") (pintype "output"))
      (node (ref "IC7") (pin "13") (pinfunction "B_13") (pintype "input"))
    )
    (net (code "236") (name "~{624}") (class "Default")
      (node (ref "IC22") (pin "13") (pinfunction "I_13") (pintype "input"))
      (node (ref "IC24") (pin "1") (pinfunction "G_1") (pintype "input"))
      (node (ref "IC24") (pin "19") (pinfunction "G_19") (pintype "input"))
      (node (ref "IC25") (pin "13") (pinfunction "Y2_13") (pintype "output"))
      (node (ref "IC38") (pin "1") (pinfunction "G_1") (pintype "input"))
    )
    (net (code "237") (name "~{641}") (class "Default")
      (node (ref "IC16") (pin "13") (pinfunction "B_13") (pintype "input"))
      (node (ref "IC32") (pin "11") (pinfunction "Y4_11") (pintype "output"))
    )
    (net (code "238") (name "~{642}") (class "Default")
      (node (ref "DAR4-7") (pin "11") (pinfunction "LD_11") (pintype "input"))
      (node (ref "DAR8-11") (pin "11") (pinfunction "LD_11") (pintype "input"))
      (node (ref "IC29") (pin "11") (pinfunction "Y4_11") (pintype "output"))
    )
    (net (code "239") (name "~{644}") (class "Default")
      (node (ref "IC16") (pin "3") (pinfunction "B_3") (pintype "input"))
      (node (ref "IC25") (pin "11") (pinfunction "Y4_11") (pintype "output"))
    )
    (net (code "240") (name "~{645}") (class "Default")
      (node (ref "IC16") (pin "4") (pinfunction "Y0_4") (pintype "output"))
      (node (ref "IC31") (pin "1") (pinfunction "G_1") (pintype "input"))
      (node (ref "IC31") (pin "19") (pinfunction "G_19") (pintype "input"))
      (node (ref "IC38") (pin "19") (pinfunction "G_19") (pintype "input"))
    )
    (net (code "241") (name "~{ACB00}") (class "Default")
      (node (ref "D34L") (pin "2") (pinfunction "2_2") (pintype "passive"))
      (node (ref "IC37") (pin "12") (pinfunction "Y4_12") (pintype "tri_state"))
      (node (ref "IC38") (pin "12") (pinfunction "Y4_12") (pintype "tri_state"))
      (node (ref "IC38") (pin "3") (pinfunction "Y4_3") (pintype "tri_state"))
    )
    (net (code "242") (name "~{ACB01}") (class "Default")
      (node (ref "D34L") (pin "4") (pinfunction "4_4") (pintype "passive"))
      (node (ref "IC37") (pin "14") (pinfunction "Y3_14") (pintype "tri_state"))
      (node (ref "IC38") (pin "14") (pinfunction "Y3_14") (pintype "tri_state"))
      (node (ref "IC38") (pin "5") (pinfunction "Y3_5") (pintype "tri_state"))
    )
    (net (code "243") (name "~{ACB02}") (class "Default")
      (node (ref "D34L") (pin "6") (pinfunction "6_6") (pintype "passive"))
      (node (ref "IC37") (pin "16") (pinfunction "Y2_16") (pintype "tri_state"))
      (node (ref "IC38") (pin "16") (pinfunction "Y2_16") (pintype "tri_state"))
      (node (ref "IC38") (pin "7") (pinfunction "Y2_7") (pintype "tri_state"))
    )
    (net (code "244") (name "~{ACB03}") (class "Default")
      (node (ref "D34L") (pin "8") (pinfunction "8_8") (pintype "passive"))
      (node (ref "IC37") (pin "18") (pinfunction "Y1_18") (pintype "tri_state"))
      (node (ref "IC38") (pin "18") (pinfunction "Y1_18") (pintype "tri_state"))
      (node (ref "IC38") (pin "9") (pinfunction "Y1_9") (pintype "tri_state"))
    )
    (net (code "245") (name "~{ACB04}") (class "Default")
      (node (ref "D34L") (pin "10") (pinfunction "10_10") (pintype "passive"))
      (node (ref "IC24") (pin "3") (pinfunction "Y4_3") (pintype "tri_state"))
      (node (ref "IC30") (pin "3") (pinfunction "Y4_3") (pintype "tri_state"))
      (node (ref "IC31") (pin "3") (pinfunction "Y4_3") (pintype "tri_state"))
    )
    (net (code "246") (name "~{ACB05}") (class "Default")
      (node (ref "D34L") (pin "12") (pinfunction "12_12") (pintype "passive"))
      (node (ref "IC24") (pin "5") (pinfunction "Y3_5") (pintype "tri_state"))
      (node (ref "IC30") (pin "5") (pinfunction "Y3_5") (pintype "tri_state"))
      (node (ref "IC31") (pin "5") (pinfunction "Y3_5") (pintype "tri_state"))
    )
    (net (code "247") (name "~{ACB06}") (class "Default")
      (node (ref "D34L") (pin "14") (pinfunction "14_14") (pintype "passive"))
      (node (ref "IC24") (pin "7") (pinfunction "Y2_7") (pintype "tri_state"))
      (node (ref "IC30") (pin "7") (pinfunction "Y2_7") (pintype "tri_state"))
      (node (ref "IC31") (pin "7") (pinfunction "Y2_7") (pintype "tri_state"))
    )
    (net (code "248") (name "~{ACB07}") (class "Default")
      (node (ref "D34L") (pin "16") (pinfunction "16_16") (pintype "passive"))
      (node (ref "IC24") (pin "9") (pinfunction "Y1_9") (pintype "tri_state"))
      (node (ref "IC30") (pin "9") (pinfunction "Y1_9") (pintype "tri_state"))
      (node (ref "IC31") (pin "9") (pinfunction "Y1_9") (pintype "tri_state"))
    )
    (net (code "249") (name "~{ACB08}") (class "Default")
      (node (ref "D34L") (pin "18") (pinfunction "18_18") (pintype "passive"))
      (node (ref "IC24") (pin "12") (pinfunction "Y4_12") (pintype "tri_state"))
      (node (ref "IC30") (pin "12") (pinfunction "Y4_12") (pintype "tri_state"))
      (node (ref "IC31") (pin "12") (pinfunction "Y4_12") (pintype "tri_state"))
    )
    (net (code "250") (name "~{ACB09}") (class "Default")
      (node (ref "D34L") (pin "22") (pinfunction "22_22") (pintype "passive"))
      (node (ref "IC24") (pin "14") (pinfunction "Y3_14") (pintype "tri_state"))
      (node (ref "IC30") (pin "14") (pinfunction "Y3_14") (pintype "tri_state"))
      (node (ref "IC31") (pin "14") (pinfunction "Y3_14") (pintype "tri_state"))
    )
    (net (code "251") (name "~{ACB10}") (class "Default")
      (node (ref "D34L") (pin "24") (pinfunction "24_24") (pintype "passive"))
      (node (ref "IC24") (pin "16") (pinfunction "Y2_16") (pintype "tri_state"))
      (node (ref "IC30") (pin "16") (pinfunction "Y2_16") (pintype "tri_state"))
      (node (ref "IC31") (pin "16") (pinfunction "Y2_16") (pintype "tri_state"))
    )
    (net (code "252") (name "~{ACB11}") (class "Default")
      (node (ref "D34L") (pin "26") (pinfunction "26_26") (pintype "passive"))
      (node (ref "IC24") (pin "18") (pinfunction "Y1_18") (pintype "tri_state"))
      (node (ref "IC30") (pin "18") (pinfunction "Y1_18") (pintype "tri_state"))
      (node (ref "IC31") (pin "18") (pinfunction "Y1_18") (pintype "tri_state"))
    )
    (net (code "253") (name "~{ACCLEAR}") (class "Default")
      (node (ref "D34L") (pin "32") (pinfunction "32_32") (pintype "passive"))
      (node (ref "IC22") (pin "12") (pinfunction "O_12") (pintype "open_collector"))
      (node (ref "IC22") (pin "2") (pinfunction "O_2") (pintype "open_collector"))
      (node (ref "IC22") (pin "4") (pinfunction "O_4") (pintype "open_collector"))
    )
    (net (code "254") (name "~{BADDAC}") (class "Default")
      (node (ref "C36L") (pin "34") (pinfunction "34_34") (pintype "passive"))
      (node (ref "IC11") (pin "1") (pinfunction "CLR_1") (pintype "input"))
    )
    (net (code "255") (name "~{BBREAK}") (class "Default")
      (node (ref "C36L") (pin "32") (pinfunction "32_32") (pintype "passive"))
      (node (ref "DMA8-11") (pin "5") (pinfunction "UP_5") (pintype "input"))
      (node (ref "IC20") (pin "19") (pinfunction "G_19") (pintype "input"))
      (node (ref "IC21") (pin "15") (pinfunction "G_15") (pintype "input"))
      (node (ref "IC41") (pin "1") (pinfunction "G_1") (pintype "input"))
      (node (ref "IC41") (pin "15") (pinfunction "G_15") (pintype "input"))
      (node (ref "IC6") (pin "1") (pinfunction "G_1") (pintype "input"))
    )
    (net (code "256") (name "~{BMB03}") (class "Default")
      (node (ref "D35L") (pin "8") (pinfunction "8_8") (pintype "passive"))
    )
    (net (code "257") (name "~{BMB04}") (class "Default")
      (node (ref "D35L") (pin "12") (pinfunction "12_12") (pintype "passive"))
    )
    (net (code "258") (name "~{BMB05}") (class "Default")
      (node (ref "D35L") (pin "16") (pinfunction "16_16") (pintype "passive"))
    )
    (net (code "259") (name "~{BMB06}") (class "Default")
      (node (ref "D35L") (pin "22") (pinfunction "22_22") (pintype "passive"))
    )
    (net (code "260") (name "~{BMB07}") (class "Default")
      (node (ref "D35L") (pin "26") (pinfunction "26_26") (pintype "passive"))
    )
    (net (code "261") (name "~{BMB08}") (class "Default")
      (node (ref "D35L") (pin "30") (pinfunction "30_30") (pintype "passive"))
    )
    (net (code "262") (name "~{BRK_RQ}") (class "Default")
      (node (ref "C36L") (pin "28") (pinfunction "28_28") (pintype "passive"))
      (node (ref "IC11") (pin "6") (pinfunction "~{Q}_6") (pintype "output"))
    )
    (net (code "263") (name "~{BRUN}") (class "Default")
      (node (ref "D34L") (pin "34") (pinfunction "34_34") (pintype "passive"))
    )
    (net (code "264") (name "~{BWCO}") (class "Default")
      (node (ref "C35L") (pin "32") (pinfunction "32_32") (pintype "passive"))
      (node (ref "IC10") (pin "13") (pinfunction "CLR_13") (pintype "input"))
      (node (ref "IC11") (pin "12") (pinfunction "D_12") (pintype "input"))
    )
    (net (code "265") (name "~{DA00}") (class "Default")
      (node (ref "C36L") (pin "2") (pinfunction "2_2") (pintype "passive"))
      (node (ref "J14") (pin "1") (pinfunction "1_1") (pintype "passive"))
    )
    (net (code "266") (name "~{DA01}") (class "Default")
      (node (ref "C36L") (pin "4") (pinfunction "4_4") (pintype "passive"))
      (node (ref "J13") (pin "1") (pinfunction "1_1") (pintype "passive"))
    )
    (net (code "267") (name "~{DA02}") (class "Default")
      (node (ref "C36L") (pin "6") (pinfunction "6_6") (pintype "passive"))
      (node (ref "J12") (pin "1") (pinfunction "1_1") (pintype "passive"))
    )
    (net (code "268") (name "~{DA03}") (class "Default")
      (node (ref "C36L") (pin "8") (pinfunction "8_8") (pintype "passive"))
      (node (ref "J11") (pin "1") (pinfunction "1_1") (pintype "passive"))
    )
    (net (code "269") (name "~{DA04}") (class "Default")
      (node (ref "C36L") (pin "10") (pinfunction "10_10") (pintype "passive"))
      (node (ref "J10") (pin "1") (pinfunction "1_1") (pintype "passive"))
    )
    (net (code "270") (name "~{DA05}") (class "Default")
      (node (ref "C36L") (pin "12") (pinfunction "12_12") (pintype "passive"))
      (node (ref "J9") (pin "1") (pinfunction "1_1") (pintype "passive"))
    )
    (net (code "271") (name "~{DA06}") (class "Default")
      (node (ref "C36L") (pin "14") (pinfunction "14_14") (pintype "passive"))
      (node (ref "J8") (pin "1") (pinfunction "1_1") (pintype "passive"))
    )
    (net (code "272") (name "~{DA07}") (class "Default")
      (node (ref "C36L") (pin "16") (pinfunction "16_16") (pintype "passive"))
      (node (ref "J7") (pin "1") (pinfunction "1_1") (pintype "passive"))
    )
    (net (code "273") (name "~{DA08}") (class "Default")
      (node (ref "C36L") (pin "18") (pinfunction "18_18") (pintype "passive"))
      (node (ref "J6") (pin "1") (pinfunction "1_1") (pintype "passive"))
    )
    (net (code "274") (name "~{DA09}") (class "Default")
      (node (ref "C36L") (pin "22") (pinfunction "22_22") (pintype "passive"))
      (node (ref "J5") (pin "1") (pinfunction "1_1") (pintype "passive"))
    )
    (net (code "275") (name "~{DA10}") (class "Default")
      (node (ref "C36L") (pin "24") (pinfunction "24_24") (pintype "passive"))
      (node (ref "J4") (pin "1") (pinfunction "1_1") (pintype "passive"))
    )
    (net (code "276") (name "~{DA11}") (class "Default")
      (node (ref "C36L") (pin "26") (pinfunction "26_26") (pintype "passive"))
      (node (ref "J3") (pin "1") (pinfunction "1_1") (pintype "passive"))
    )
    (net (code "277") (name "~{DATA00}") (class "Default")
      (node (ref "C35L") (pin "2") (pinfunction "2_2") (pintype "passive"))
      (node (ref "IC34") (pin "12") (pinfunction "Y4_12") (pintype "tri_state"))
    )
    (net (code "278") (name "~{DATA01}") (class "Default")
      (node (ref "C35L") (pin "4") (pinfunction "4_4") (pintype "passive"))
      (node (ref "IC34") (pin "14") (pinfunction "Y3_14") (pintype "tri_state"))
    )
    (net (code "279") (name "~{DATA02}") (class "Default")
      (node (ref "C35L") (pin "6") (pinfunction "6_6") (pintype "passive"))
      (node (ref "IC34") (pin "16") (pinfunction "Y2_16") (pintype "tri_state"))
    )
    (net (code "280") (name "~{DATA03}") (class "Default")
      (node (ref "C35L") (pin "8") (pinfunction "8_8") (pintype "passive"))
      (node (ref "IC34") (pin "18") (pinfunction "Y1_18") (pintype "tri_state"))
    )
    (net (code "281") (name "~{DATA04}") (class "Default")
      (node (ref "C35L") (pin "10") (pinfunction "10_10") (pintype "passive"))
      (node (ref "IC26") (pin "3") (pinfunction "Y4_3") (pintype "tri_state"))
    )
    (net (code "282") (name "~{DATA05}") (class "Default")
      (node (ref "C35L") (pin "12") (pinfunction "12_12") (pintype "passive"))
      (node (ref "IC26") (pin "5") (pinfunction "Y3_5") (pintype "tri_state"))
    )
    (net (code "283") (name "~{DATA06}") (class "Default")
      (node (ref "C35L") (pin "14") (pinfunction "14_14") (pintype "passive"))
      (node (ref "IC26") (pin "7") (pinfunction "Y2_7") (pintype "tri_state"))
    )
    (net (code "284") (name "~{DATA07}") (class "Default")
      (node (ref "C35L") (pin "16") (pinfunction "16_16") (pintype "passive"))
      (node (ref "IC26") (pin "9") (pinfunction "Y1_9") (pintype "tri_state"))
    )
    (net (code "285") (name "~{DATA08}") (class "Default")
      (node (ref "C35L") (pin "18") (pinfunction "18_18") (pintype "passive"))
      (node (ref "IC26") (pin "12") (pinfunction "Y4_12") (pintype "tri_state"))
    )
    (net (code "286") (name "~{DATA09}") (class "Default")
      (node (ref "C35L") (pin "22") (pinfunction "22_22") (pintype "passive"))
      (node (ref "IC26") (pin "14") (pinfunction "Y3_14") (pintype "tri_state"))
    )
    (net (code "287") (name "~{DATA10}") (class "Default")
      (node (ref "C35L") (pin "24") (pinfunction "24_24") (pintype "passive"))
      (node (ref "IC26") (pin "16") (pinfunction "Y2_16") (pintype "tri_state"))
    )
    (net (code "288") (name "~{DATA11}") (class "Default")
      (node (ref "C35L") (pin "26") (pinfunction "26_26") (pintype "passive"))
      (node (ref "IC26") (pin "18") (pinfunction "Y1_18") (pintype "tri_state"))
    )
    (net (code "289") (name "~{DCXA}") (class "Default")
      (node (ref "IC16") (pin "12") (pinfunction "Y0_12") (pintype "output"))
      (node (ref "IC18") (pin "10") (pinfunction "I1_10") (pintype "input"))
      (node (ref "IC18") (pin "9") (pinfunction "I0_9") (pintype "input"))
    )
    (net (code "290") (name "~{DIMA}") (class "Default")
      (node (ref "IC17") (pin "11") (pinfunction "Y1_11") (pintype "output"))
      (node (ref "IC30") (pin "1") (pinfunction "G_1") (pintype "input"))
      (node (ref "IC30") (pin "19") (pinfunction "G_19") (pintype "input"))
      (node (ref "IC37") (pin "1") (pinfunction "G_1") (pintype "input"))
    )
    (net (code "291") (name "~{DIML}") (class "Default")
      (node (ref "FIELD") (pin "11") (pinfunction "LD_11") (pintype "input"))
      (node (ref "IC17") (pin "12") (pinfunction "Y0_12") (pintype "output"))
      (node (ref "INTENB") (pin "11") (pinfunction "LD_11") (pintype "input"))
    )
    (net (code "292") (name "~{DMA-IN}") (class "Default")
      (node (ref "IC13") (pin "4") (pinfunction "OI_4") (pintype "input"))
      (node (ref "IC26") (pin "1") (pinfunction "G_1") (pintype "input"))
      (node (ref "IC26") (pin "19") (pinfunction "G_19") (pintype "input"))
      (node (ref "IC34") (pin "1") (pinfunction "G_1") (pintype "input"))
      (node (ref "IC41") (pin "12") (pinfunction "Y0_12") (pintype "output"))
    )
    (net (code "293") (name "~{DMA-OUT}") (class "Default")
      (node (ref "IC28") (pin "1") (pinfunction "G_1") (pintype "input"))
      (node (ref "IC28") (pin "19") (pinfunction "G_19") (pintype "input"))
      (node (ref "IC35") (pin "1") (pinfunction "G_1") (pintype "input"))
      (node (ref "IC35") (pin "19") (pinfunction "G_19") (pintype "input"))
      (node (ref "IC41") (pin "9") (pinfunction "Y3_9") (pintype "output"))
    )
    (net (code "294") (name "~{DRV01}") (class "Default")
      (node (ref "IC41") (pin "4") (pinfunction "Y0_4") (pintype "output"))
      (node (ref "RS08") (pin "38") (pinfunction "38_38") (pintype "passive"))
    )
    (net (code "295") (name "~{DRV23}") (class "Default")
      (node (ref "IC41") (pin "7") (pinfunction "Y3_7") (pintype "output"))
      (node (ref "RS08") (pin "22") (pinfunction "22_22") (pintype "passive"))
    )
    (net (code "296") (name "~{DRVOK}") (class "Default")
      (node (ref "IC21") (pin "13") (pinfunction "B_13") (pintype "input"))
      (node (ref "IC21") (pin "14") (pinfunction "A_14") (pintype "input"))
      (node (ref "R2") (pin "1") (pinfunction "1_1") (pintype "passive"))
      (node (ref "RS08") (pin "40") (pinfunction "40_40") (pintype "passive"))
    )
    (net (code "297") (name "~{EXAD0}") (class "Default")
      (node (ref "C35L") (pin "34") (pinfunction "34_34") (pintype "passive"))
      (node (ref "IC20") (pin "9") (pinfunction "Y1_9") (pintype "tri_state"))
    )
    (net (code "298") (name "~{EXAD1}") (class "Default")
      (node (ref "C35L") (pin "36") (pinfunction "36_36") (pintype "passive"))
      (node (ref "IC20") (pin "7") (pinfunction "Y2_7") (pintype "tri_state"))
    )
    (net (code "299") (name "~{EXAD2}") (class "Default")
      (node (ref "C35L") (pin "38") (pinfunction "38_38") (pintype "passive"))
      (node (ref "IC20") (pin "5") (pinfunction "Y3_5") (pintype "tri_state"))
    )
    (net (code "300") (name "~{INT_RQ}") (class "Default")
      (node (ref "D34L") (pin "30") (pinfunction "30_30") (pintype "passive"))
      (node (ref "IC40") (pin "3") (pinfunction "O_3") (pintype "open_collector"))
      (node (ref "IC40") (pin "6") (pinfunction "O_6") (pintype "open_collector"))
      (node (ref "IC40") (pin "8") (pinfunction "O_8") (pintype "open_collector"))
    )
    (net (code "301") (name "~{IOS}") (class "Default")
      (node (ref "D34L") (pin "28") (pinfunction "28_28") (pintype "passive"))
      (node (ref "IC22") (pin "10") (pinfunction "O_10") (pintype "open_collector"))
    )
    (net (code "302") (name "~{MEM_INC}") (class "Default")
      (node (ref "C36L") (pin "36") (pinfunction "36_36") (pintype "passive"))
    )
    (net (code "303") (name "~{MYDEV}") (class "Default")
      (node (ref "IC25") (pin "4") (pinfunction "G2A_4") (pintype "input"))
      (node (ref "IC29") (pin "4") (pinfunction "G2A_4") (pintype "input"))
      (node (ref "IC32") (pin "4") (pinfunction "G2A_4") (pintype "input"))
      (node (ref "PAD1") (pin "1") (pinfunction "P_1") (pintype "passive"))
    )
    (net (code "304") (name "~{NXD}") (class "Default")
      (node (ref "IC12") (pin "12") (pinfunction "I0_12") (pintype "input"))
      (node (ref "IC23") (pin "6") (pinfunction "~{Q}_6") (pintype "output"))
    )
    (net (code "305") (name "~{PER}") (class "Default")
      (node (ref "IC12") (pin "4") (pinfunction "I0_4") (pintype "input"))
      (node (ref "IC9") (pin "8") (pinfunction "~{Q}_8") (pintype "output"))
    )
    (net (code "306") (name "~{SETNXD}") (class "Default")
      (node (ref "IC21") (pin "9") (pinfunction "Y3_9") (pintype "output"))
      (node (ref "IC23") (pin "4") (pinfunction "PRE_4") (pintype "input"))
    )
    (net (code "307") (name "~{SETPER}") (class "Default")
      (node (ref "IC13") (pin "5") (pinfunction "EVN_5") (pintype "output"))
      (node (ref "IC9") (pin "10") (pinfunction "PRE_10") (pintype "input"))
    )
    (net (code "308") (name "~{SETWLS}") (class "Default")
      (node (ref "IC6") (pin "7") (pinfunction "Y3_7") (pintype "output"))
      (node (ref "IC9") (pin "4") (pinfunction "PRE_4") (pintype "input"))
    )
    (net (code "309") (name "~{SKIP}") (class "Default")
      (node (ref "IC17") (pin "2") (pinfunction "A_2") (pintype "input"))
      (node (ref "IC19") (pin "10") (pinfunction "O_10") (pintype "open_collector"))
      (node (ref "IC19") (pin "2") (pinfunction "O_2") (pintype "open_collector"))
      (node (ref "IC19") (pin "6") (pinfunction "O_6") (pintype "open_collector"))
      (node (ref "R1") (pin "1") (pinfunction "1_1") (pintype "passive"))
    )
    (net (code "310") (name "~{START}") (class "Default")
      (node (ref "DMA0-3") (pin "11") (pinfunction "LD_11") (pintype "input"))
      (node (ref "DMA4-7") (pin "11") (pinfunction "LD_11") (pintype "input"))
      (node (ref "DMA8-11") (pin "11") (pinfunction "LD_11") (pintype "input"))
      (node (ref "IC18") (pin "3") (pinfunction "O_3") (pintype "output"))
    )
    (net (code "311") (name "~{WE}") (class "Default")
      (node (ref "IC22") (pin "5") (pinfunction "I_5") (pintype "input"))
      (node (ref "IC6") (pin "5") (pinfunction "Y1_5") (pintype "output"))
      (node (ref "RS08") (pin "8") (pinfunction "8_8") (pintype "passive"))
    )
    (net (code "312") (name "~{WLS}") (class "Default")
      (node (ref "IC12") (pin "13") (pinfunction "I1_13") (pintype "input"))
      (node (ref "IC9") (pin "6") (pinfunction "~{Q}_6") (pintype "output"))
    )
  )
)
